# CoreBoard-001_2024-04-29.net
KiCad netlist of a schematic drawn in EasyEDA Pro
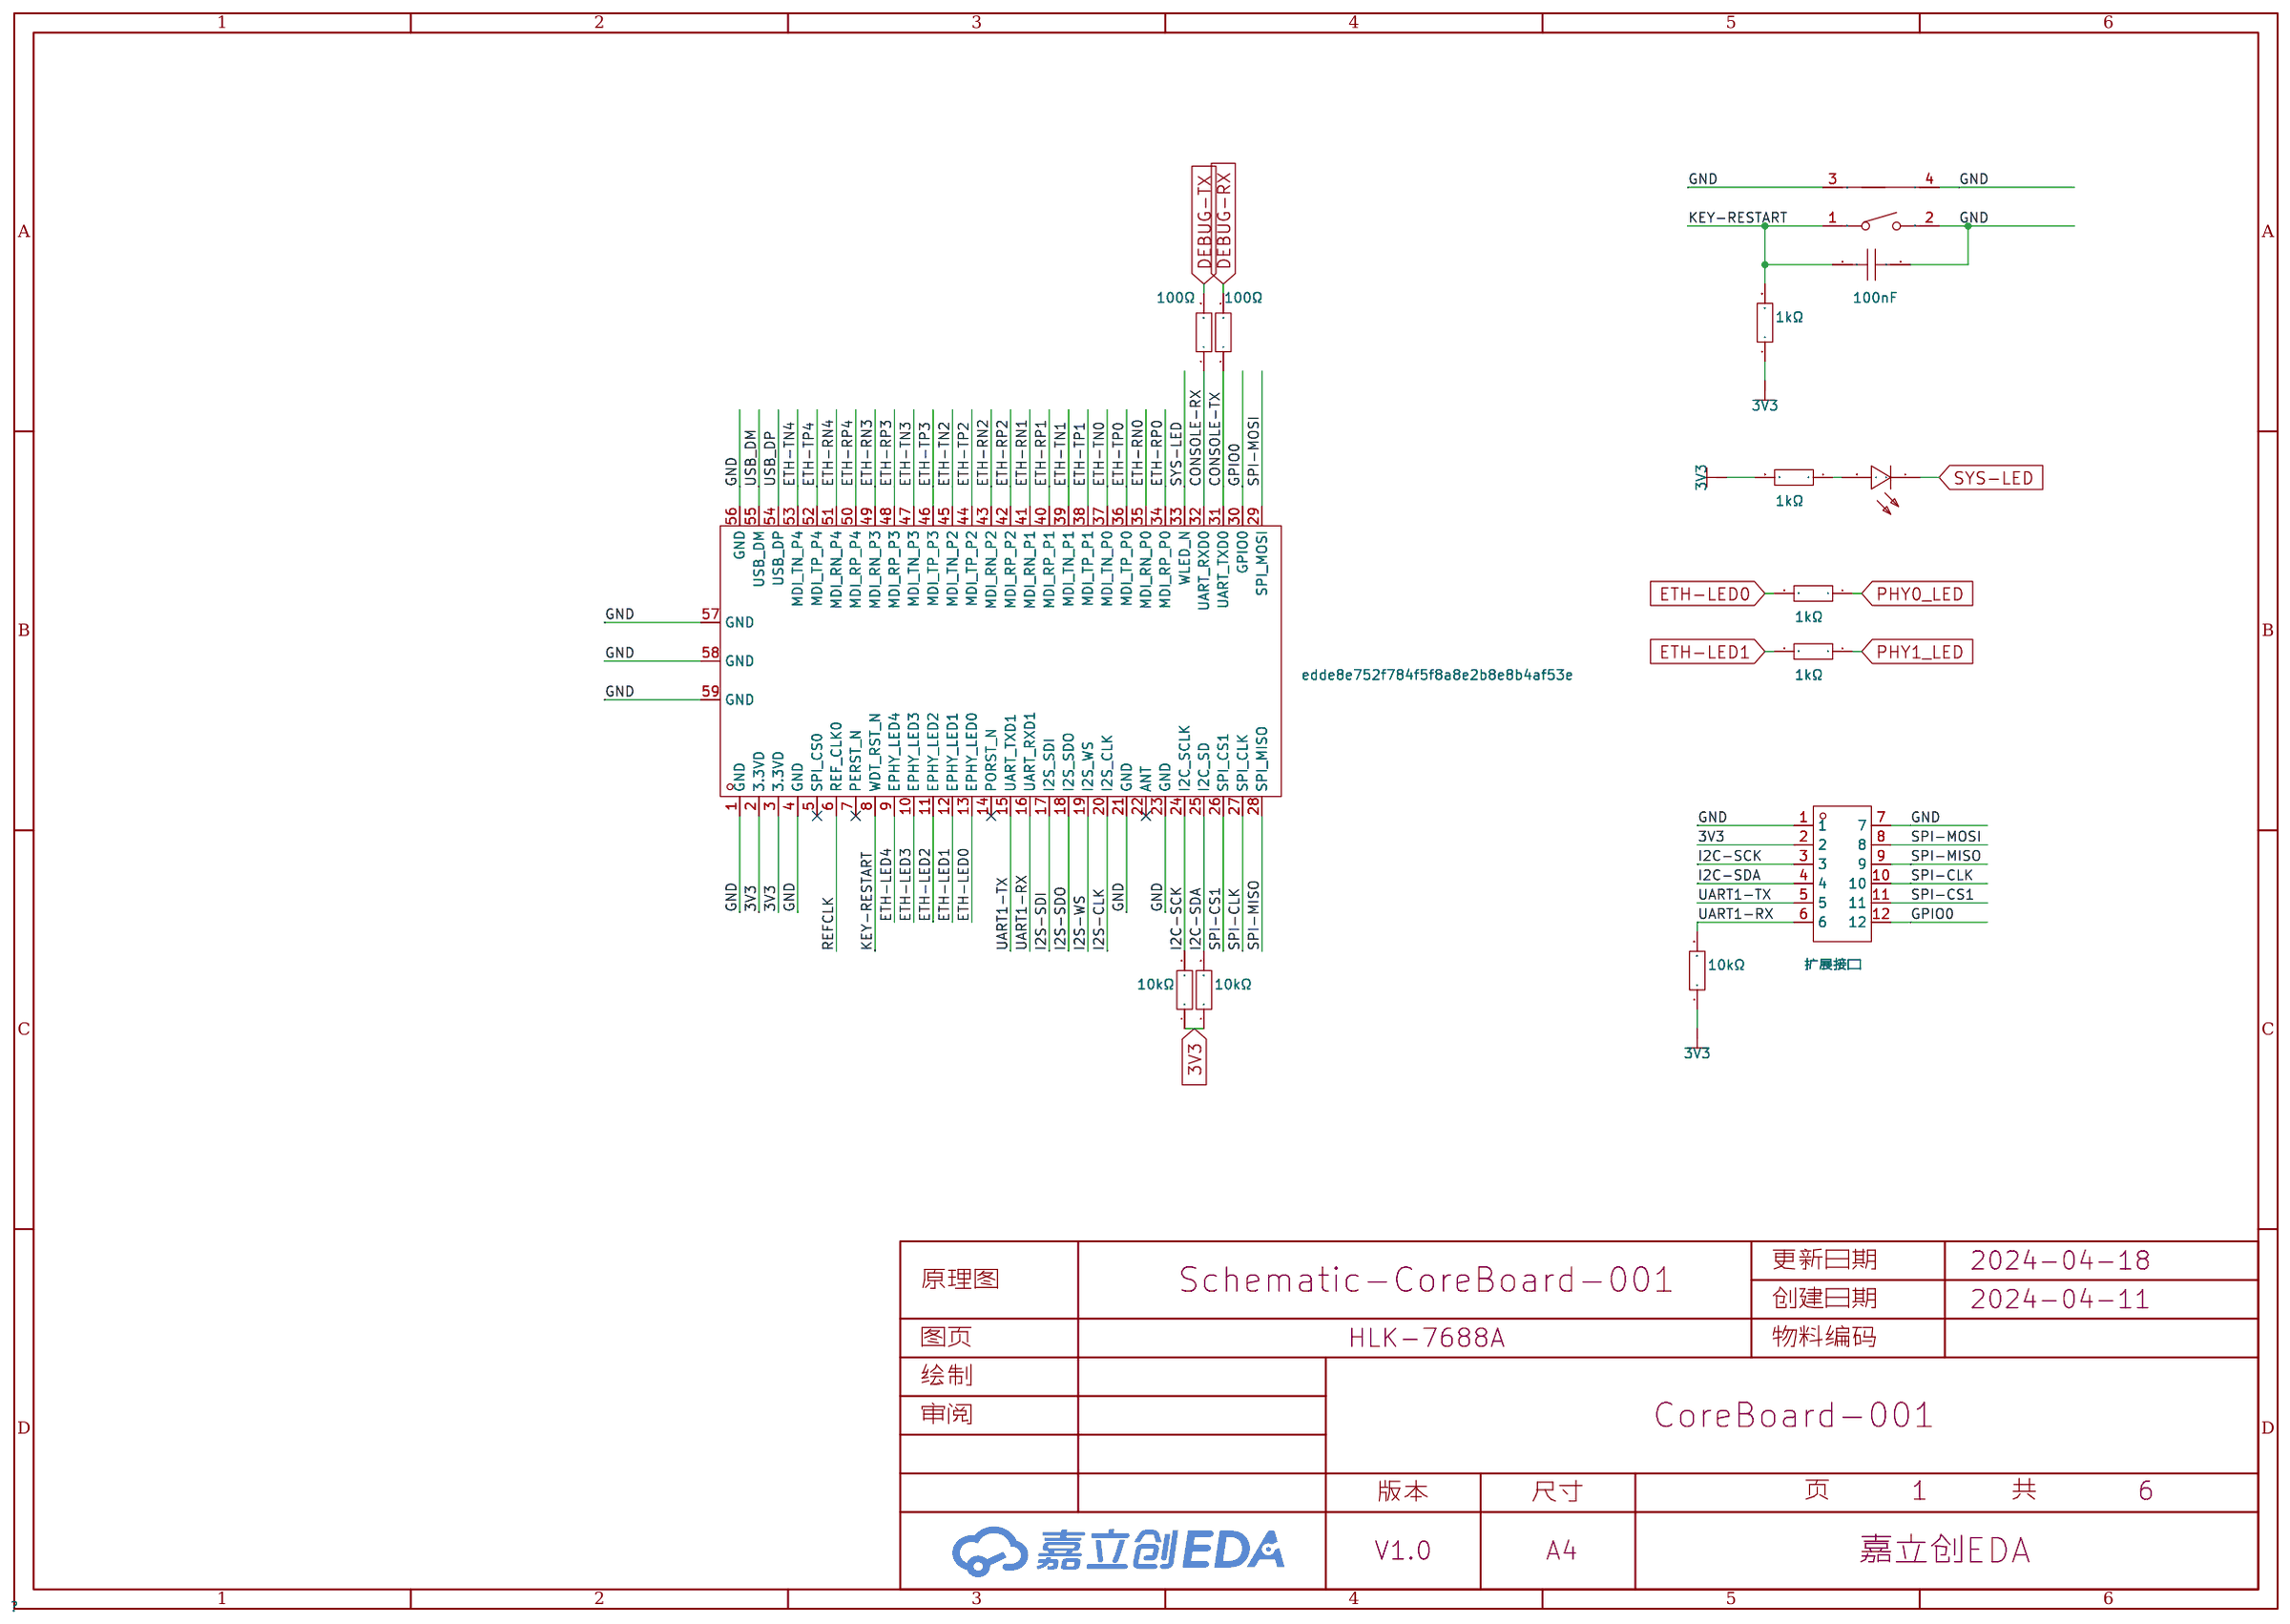
[diagram p0: HLK-7688A]
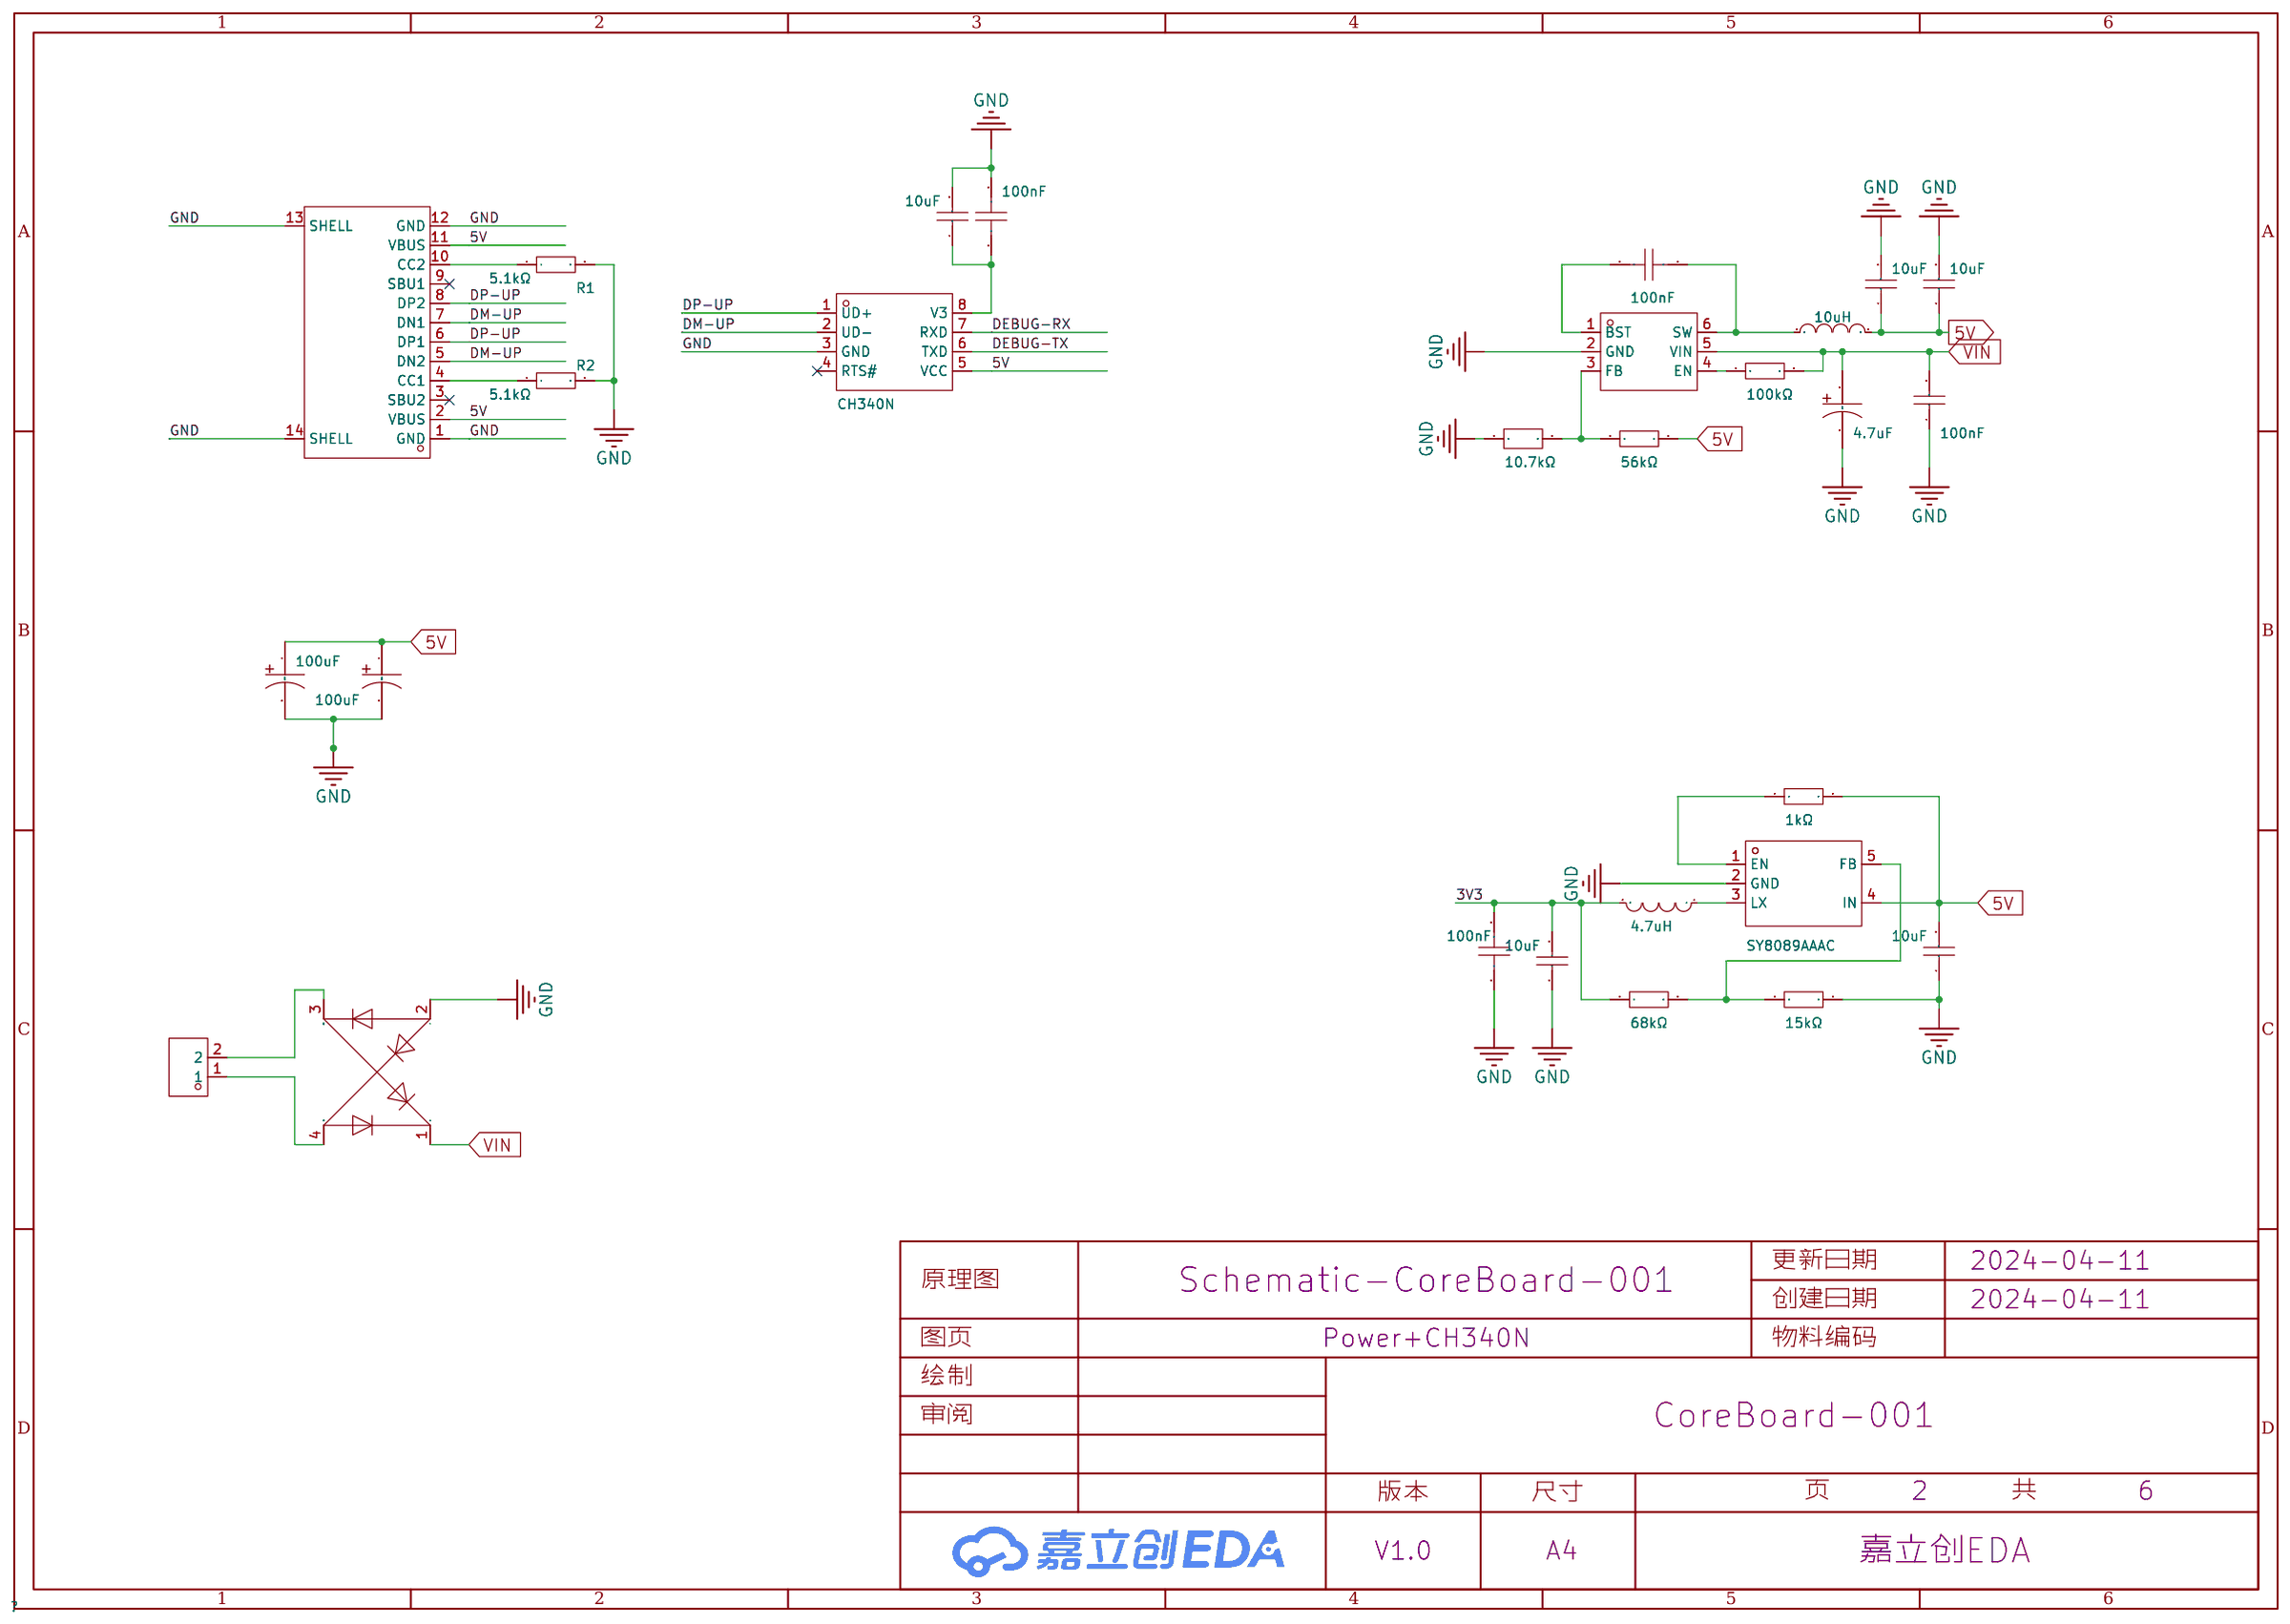
[diagram p1: Power+CH340N]
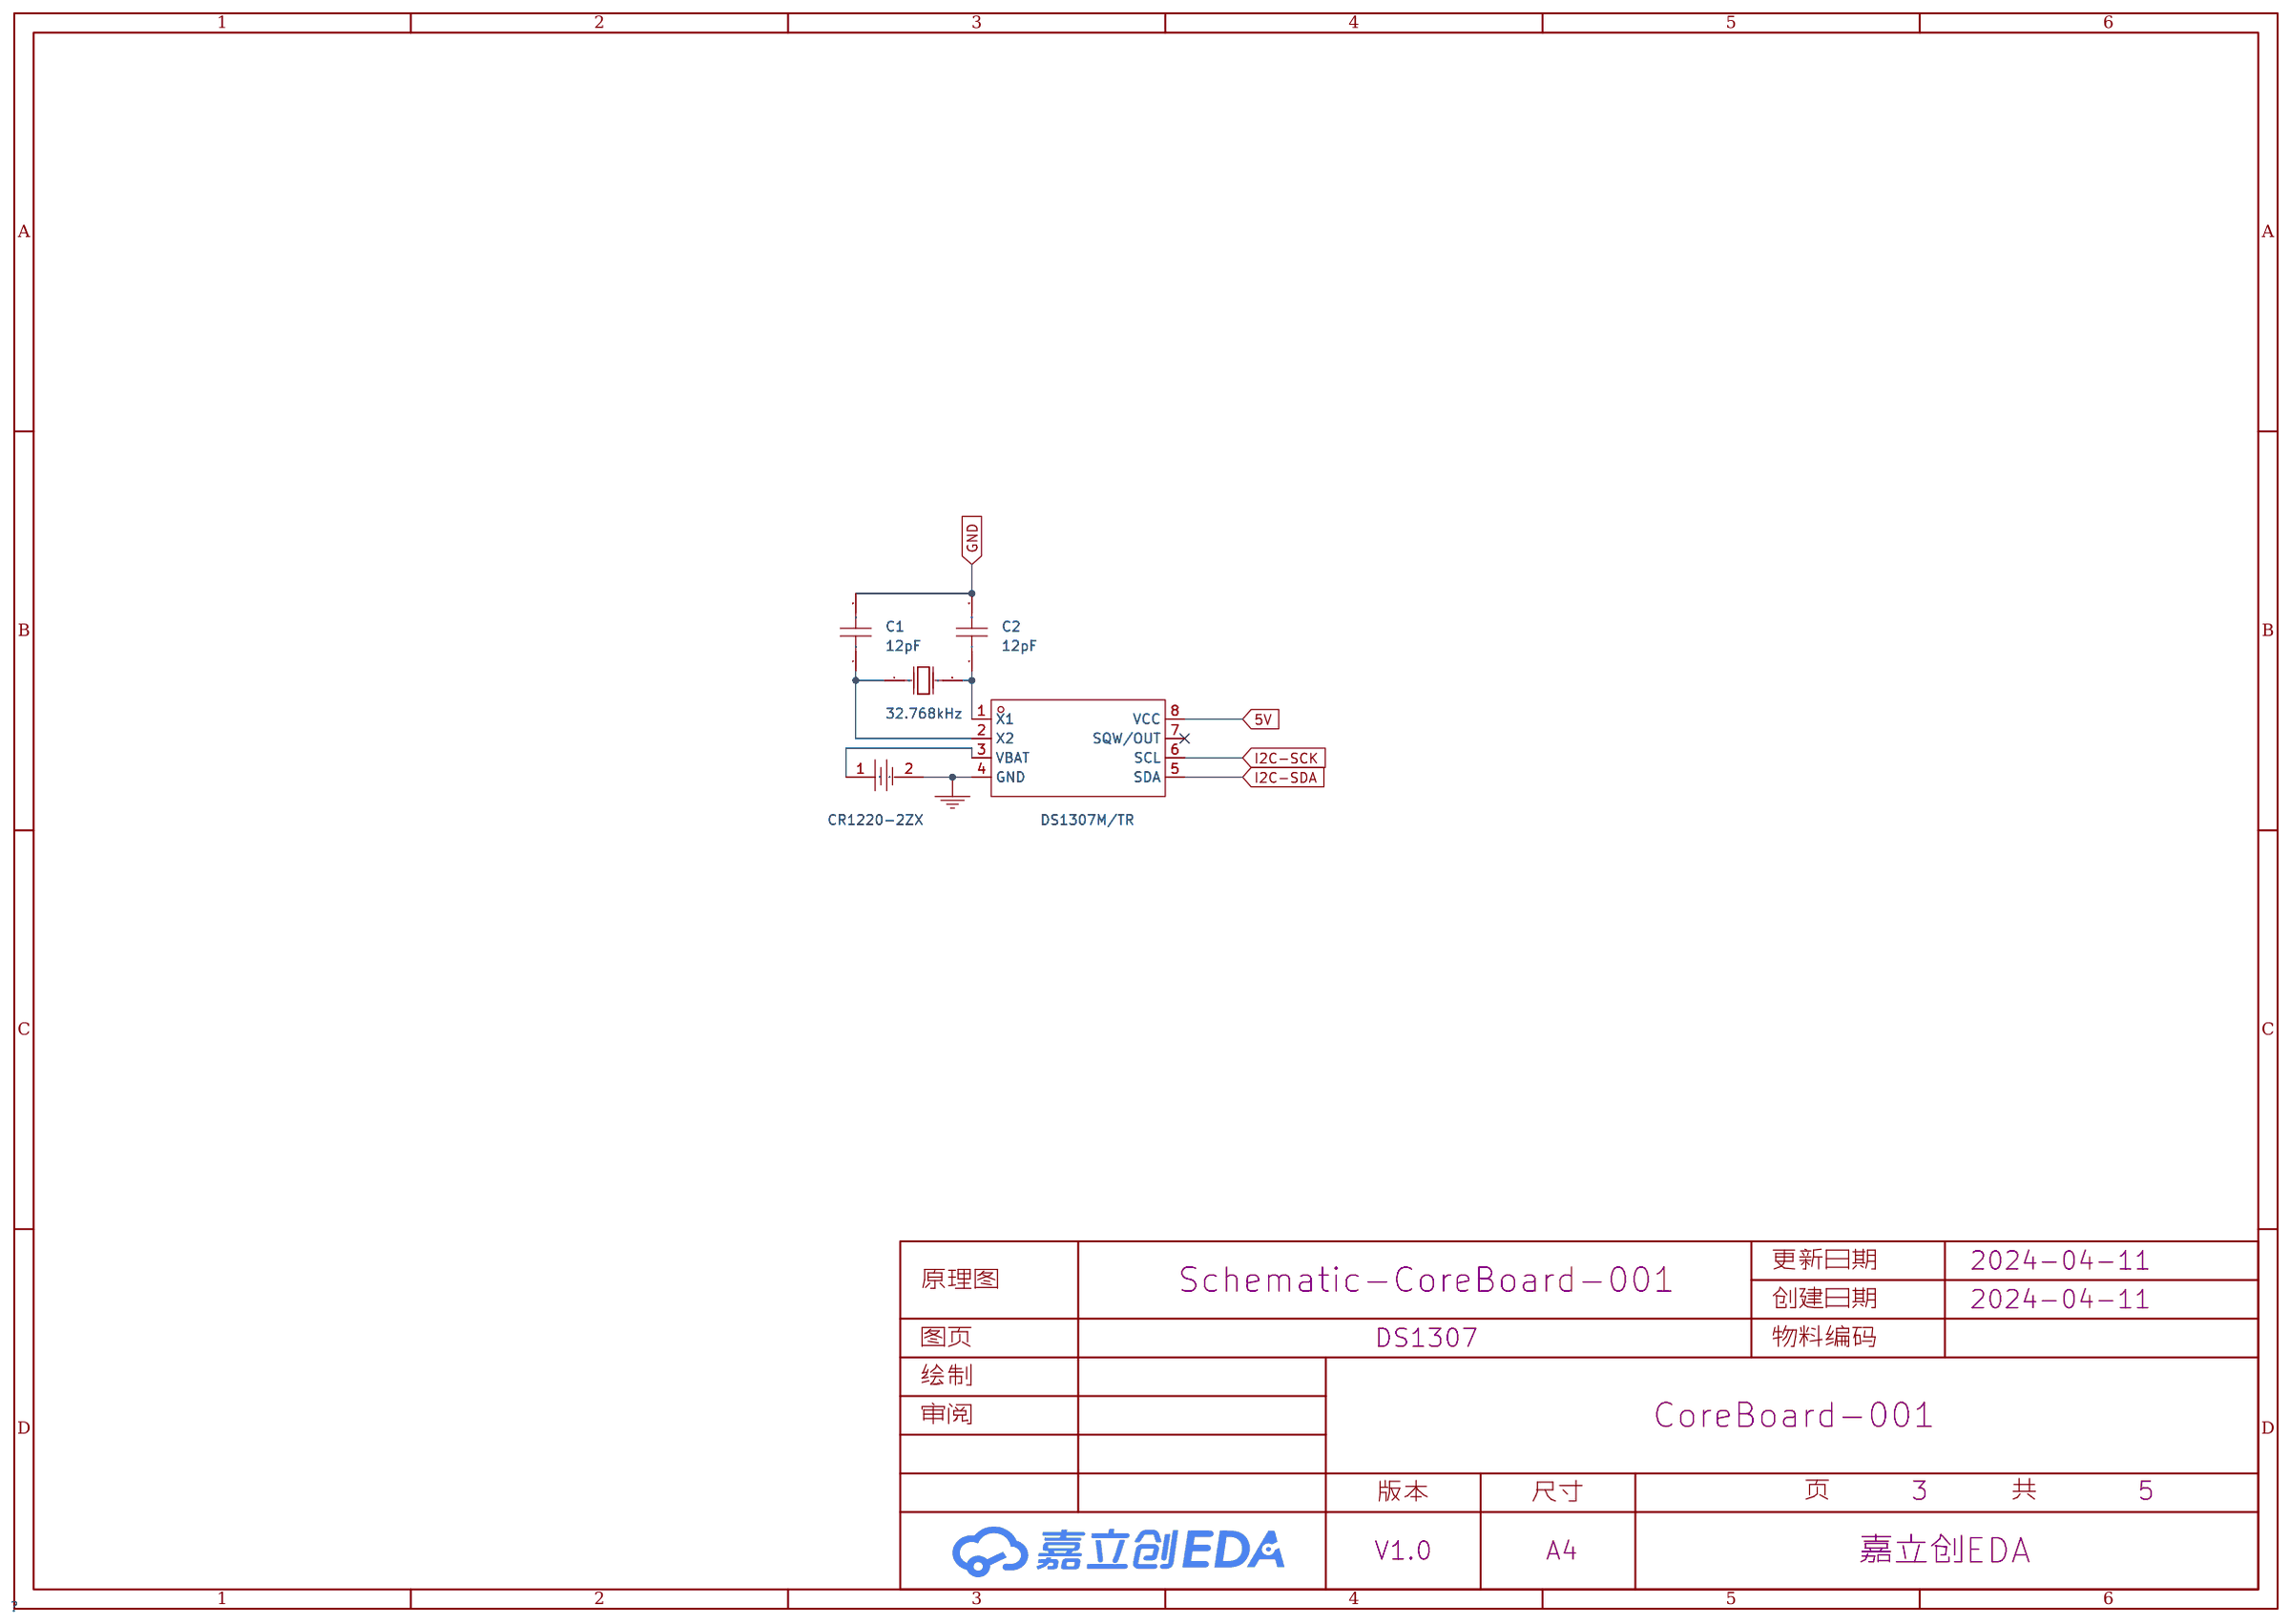
[diagram p2: DS1307]
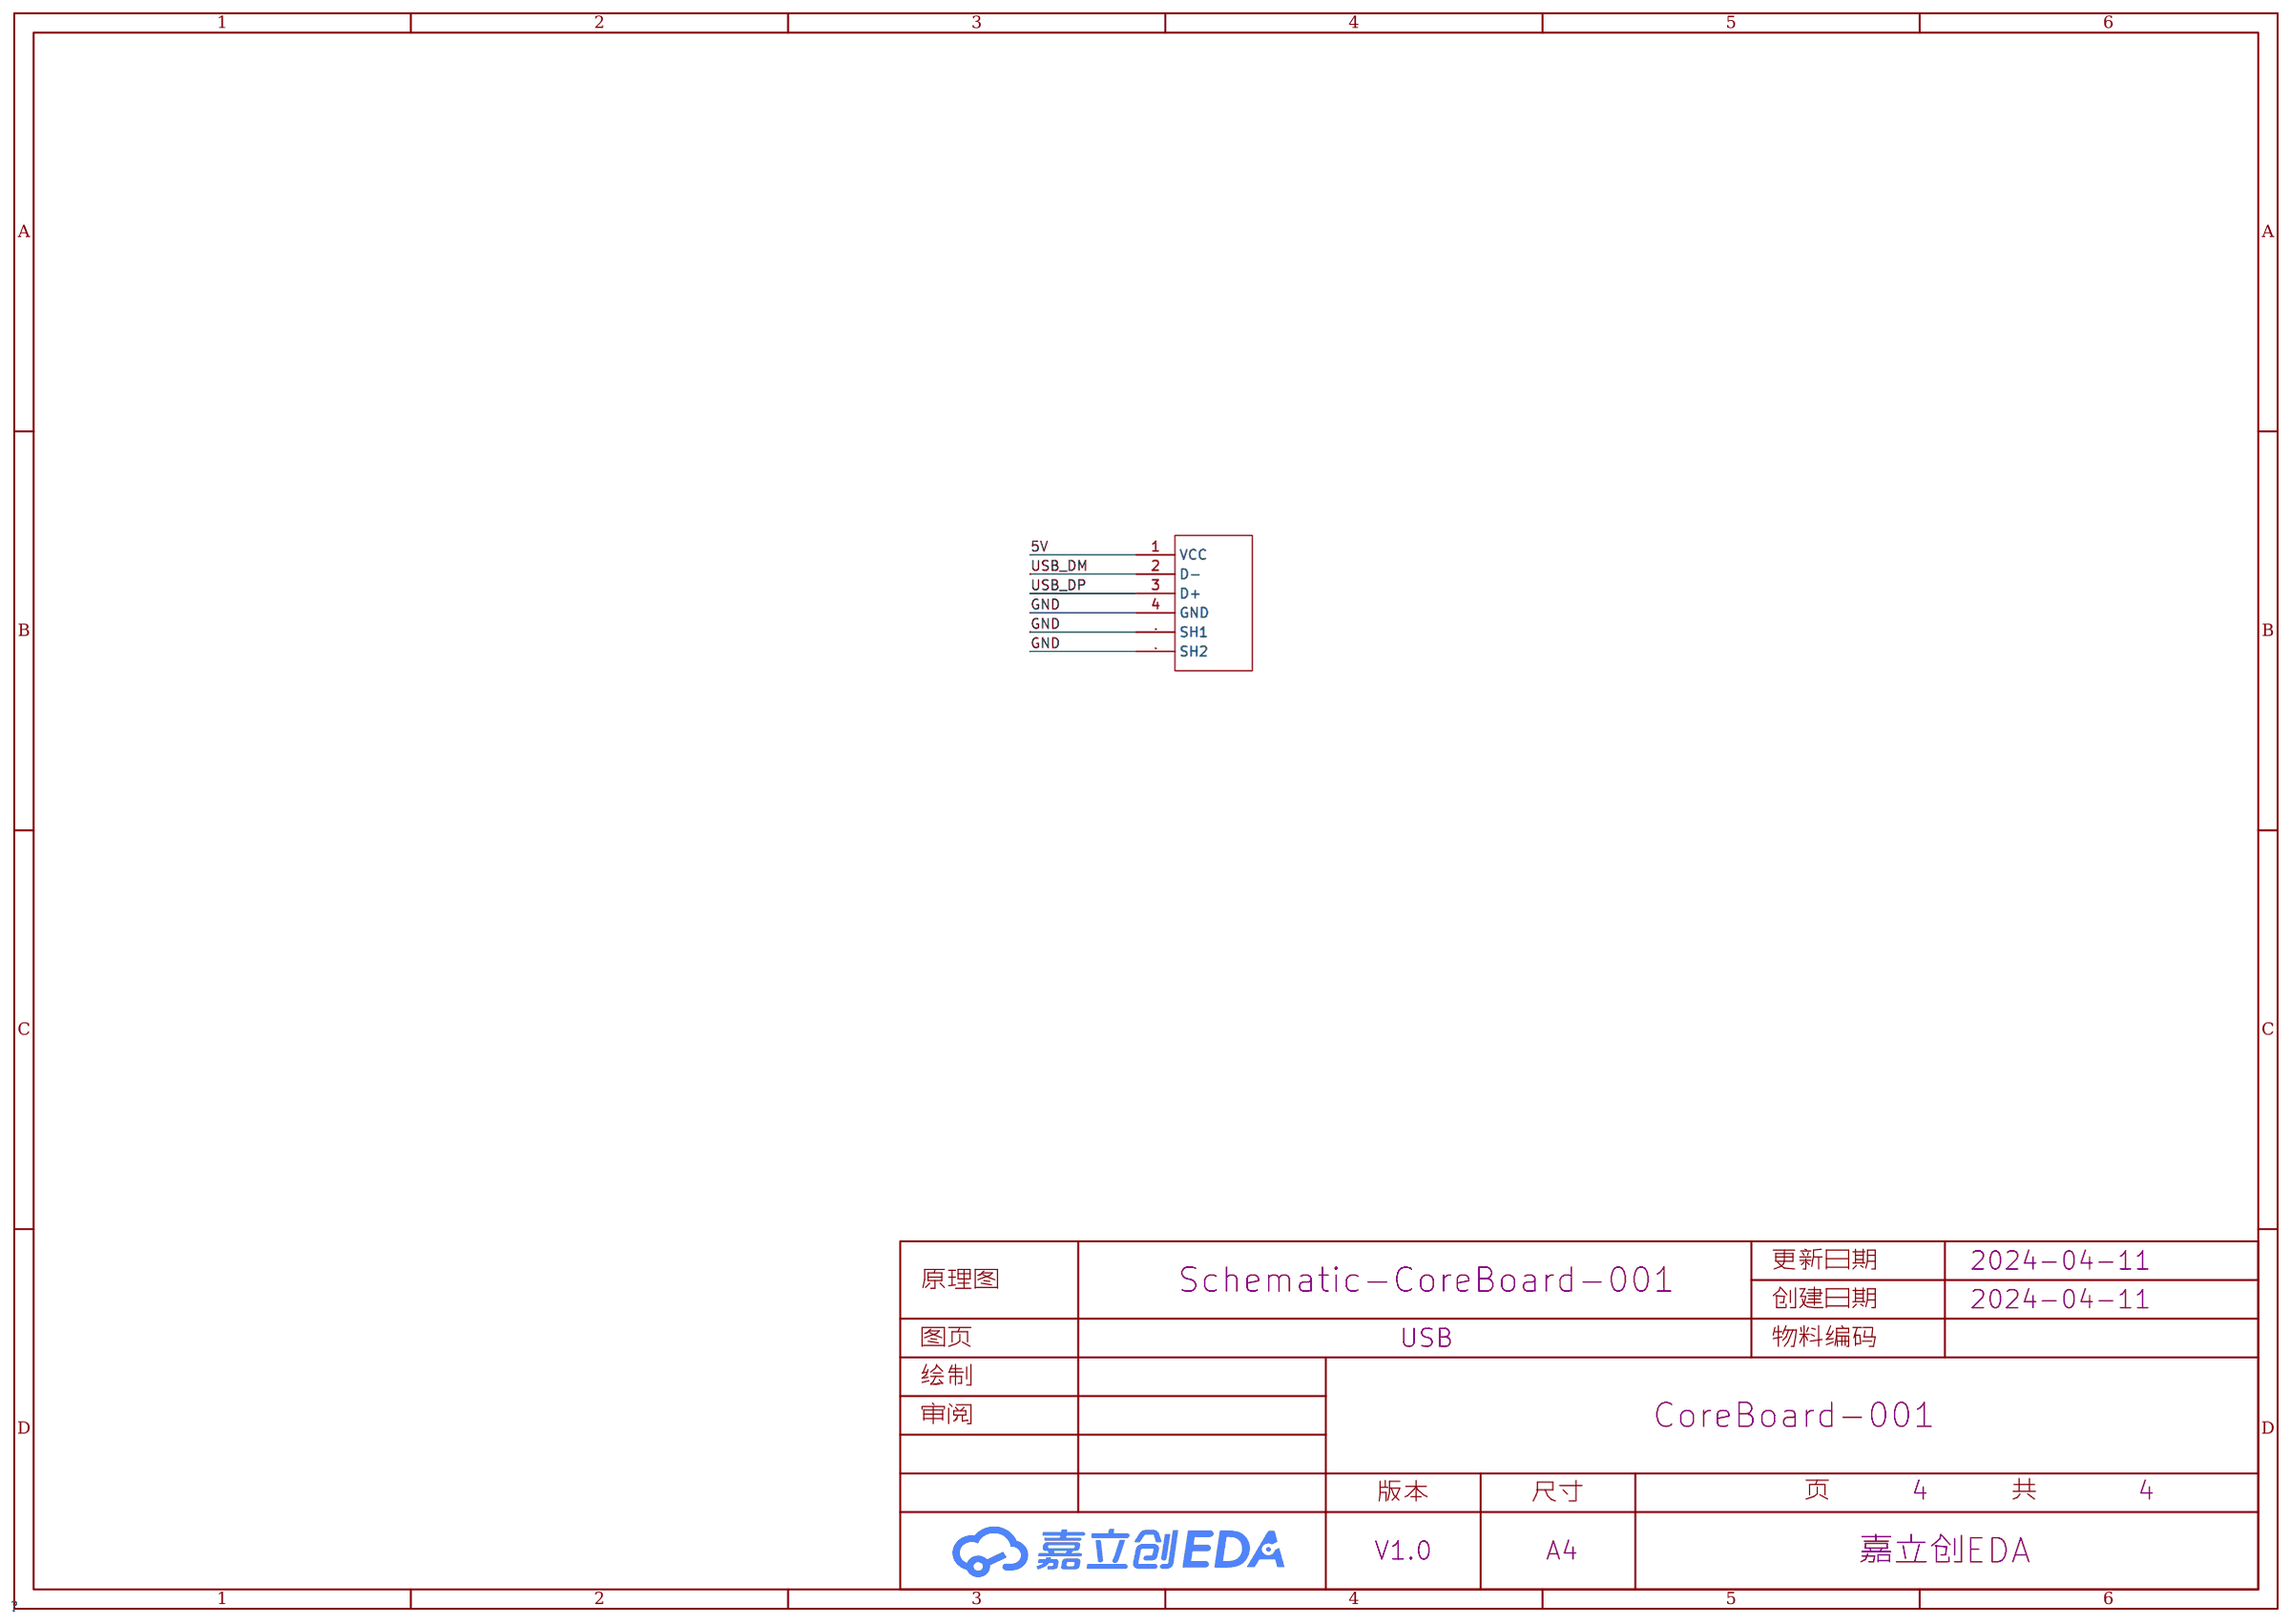
[diagram p3: USB]
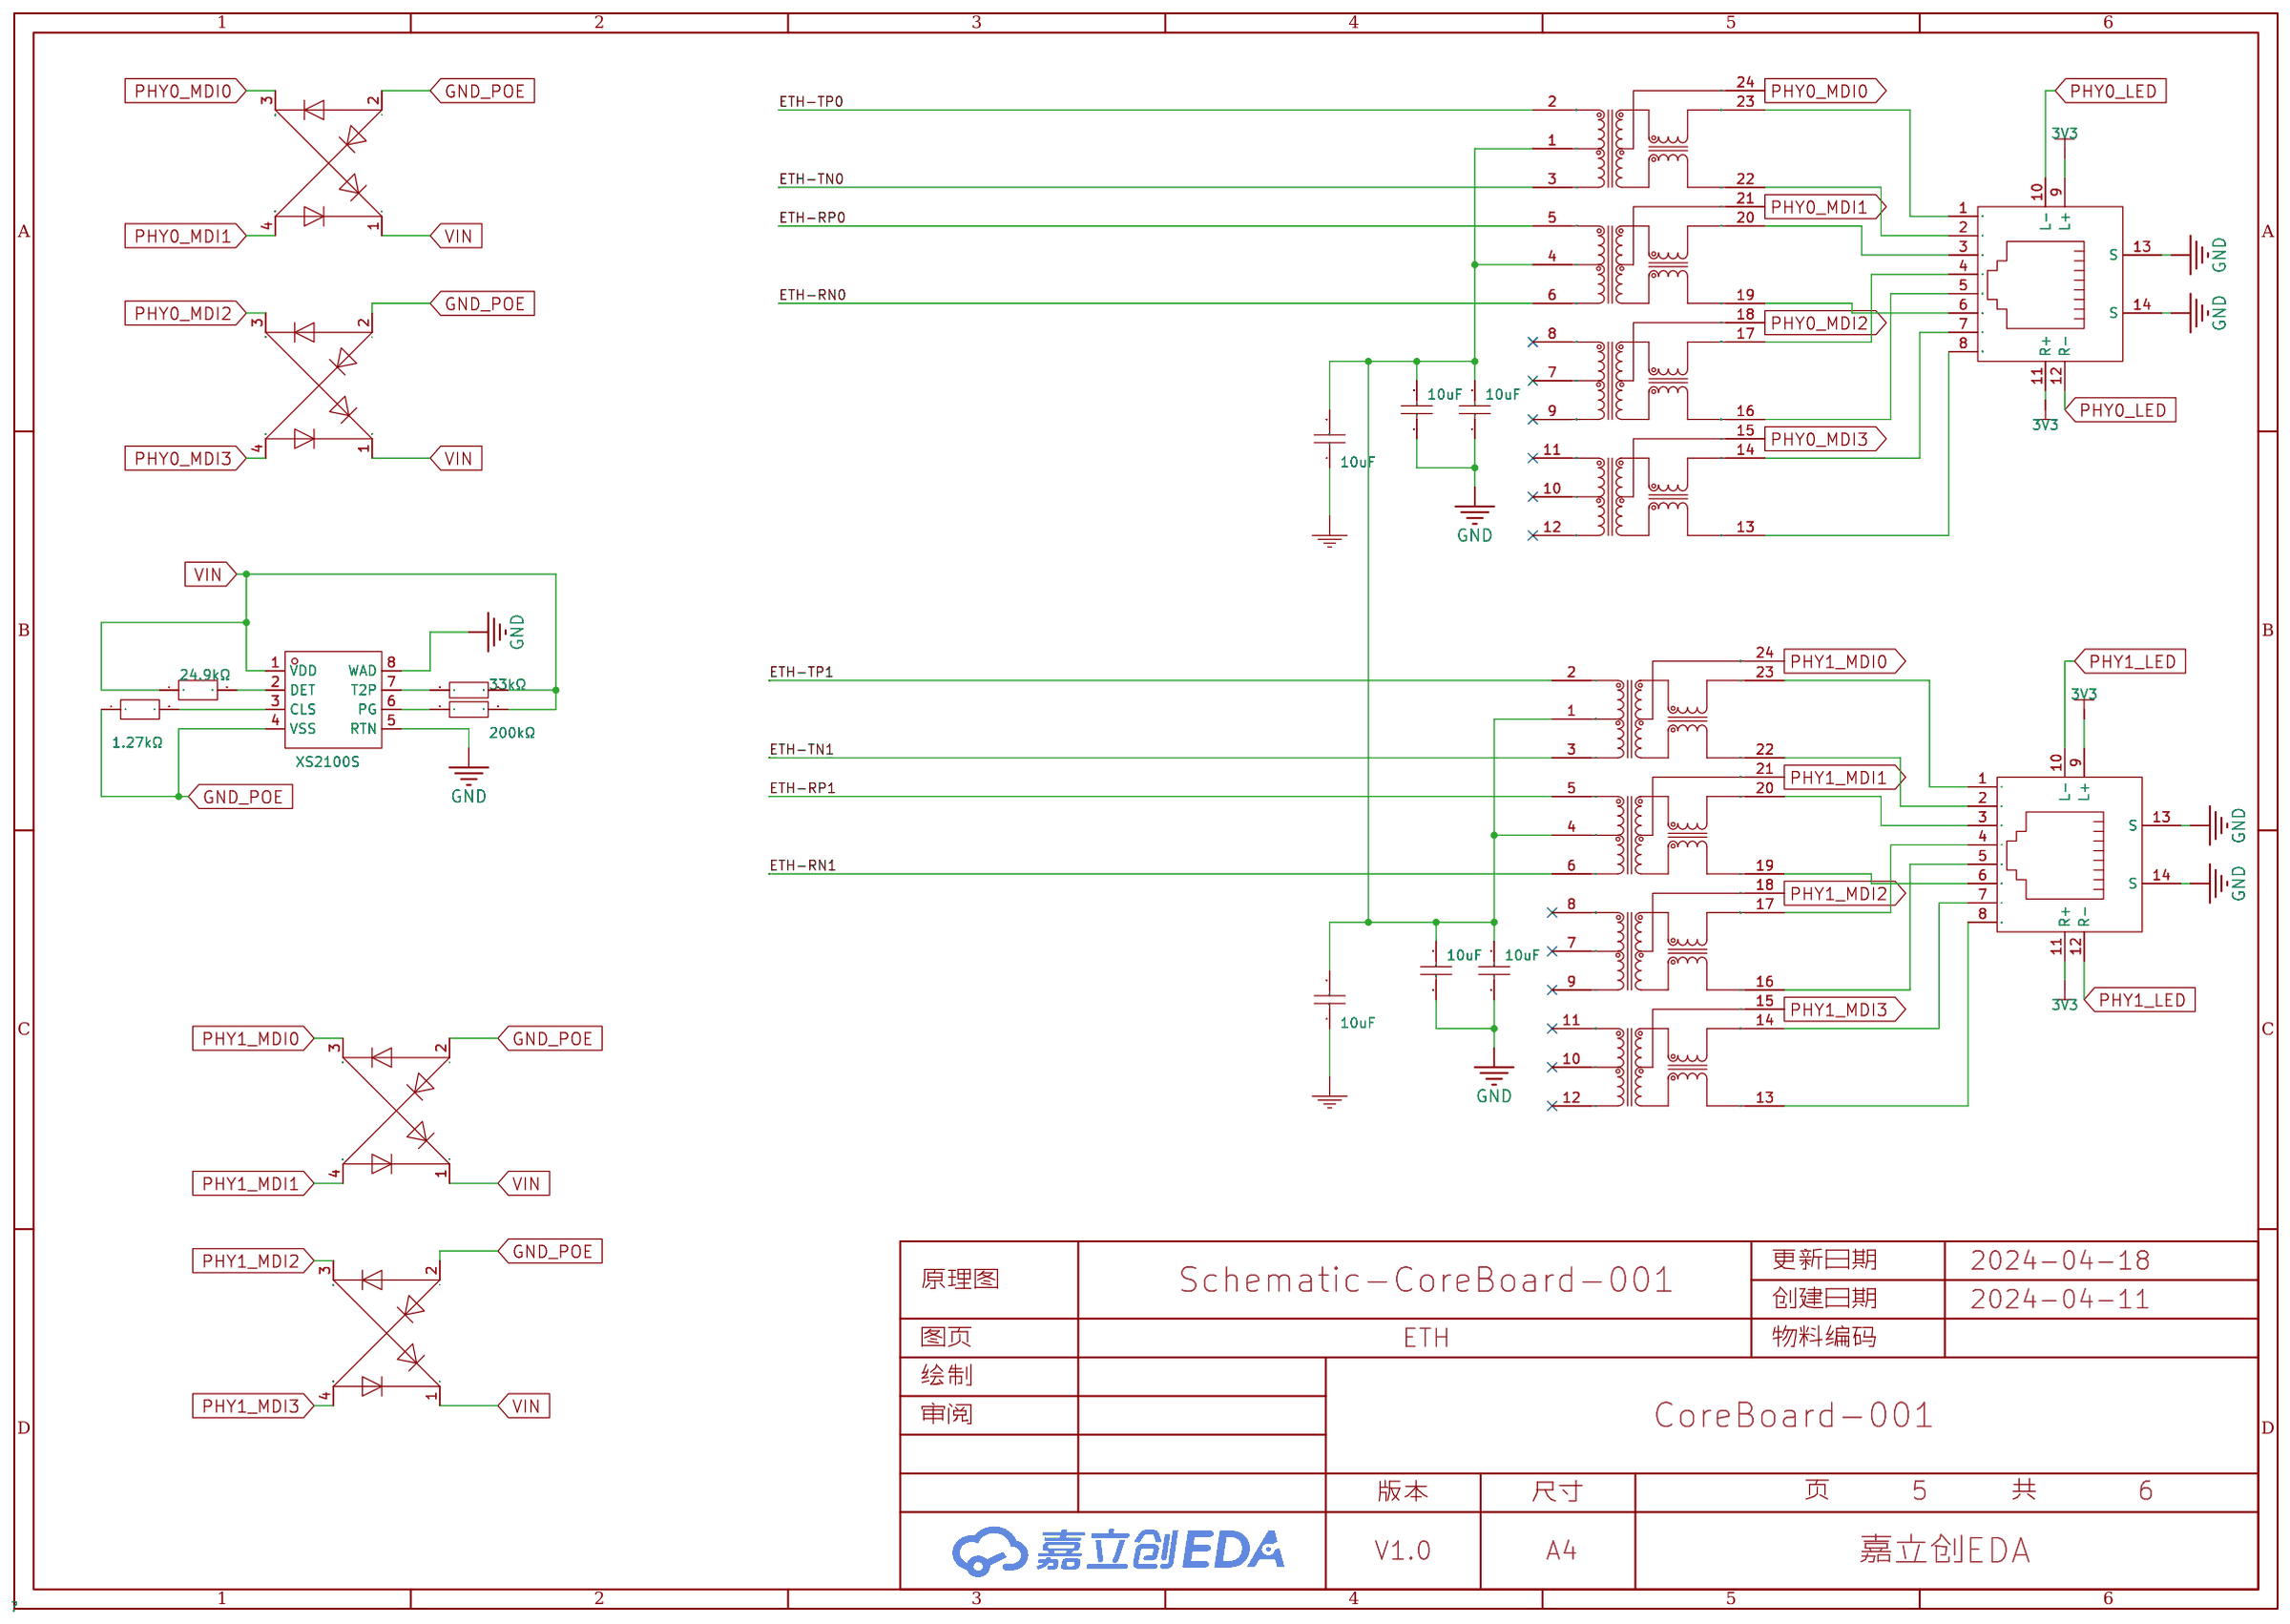
[diagram p4: ETH]
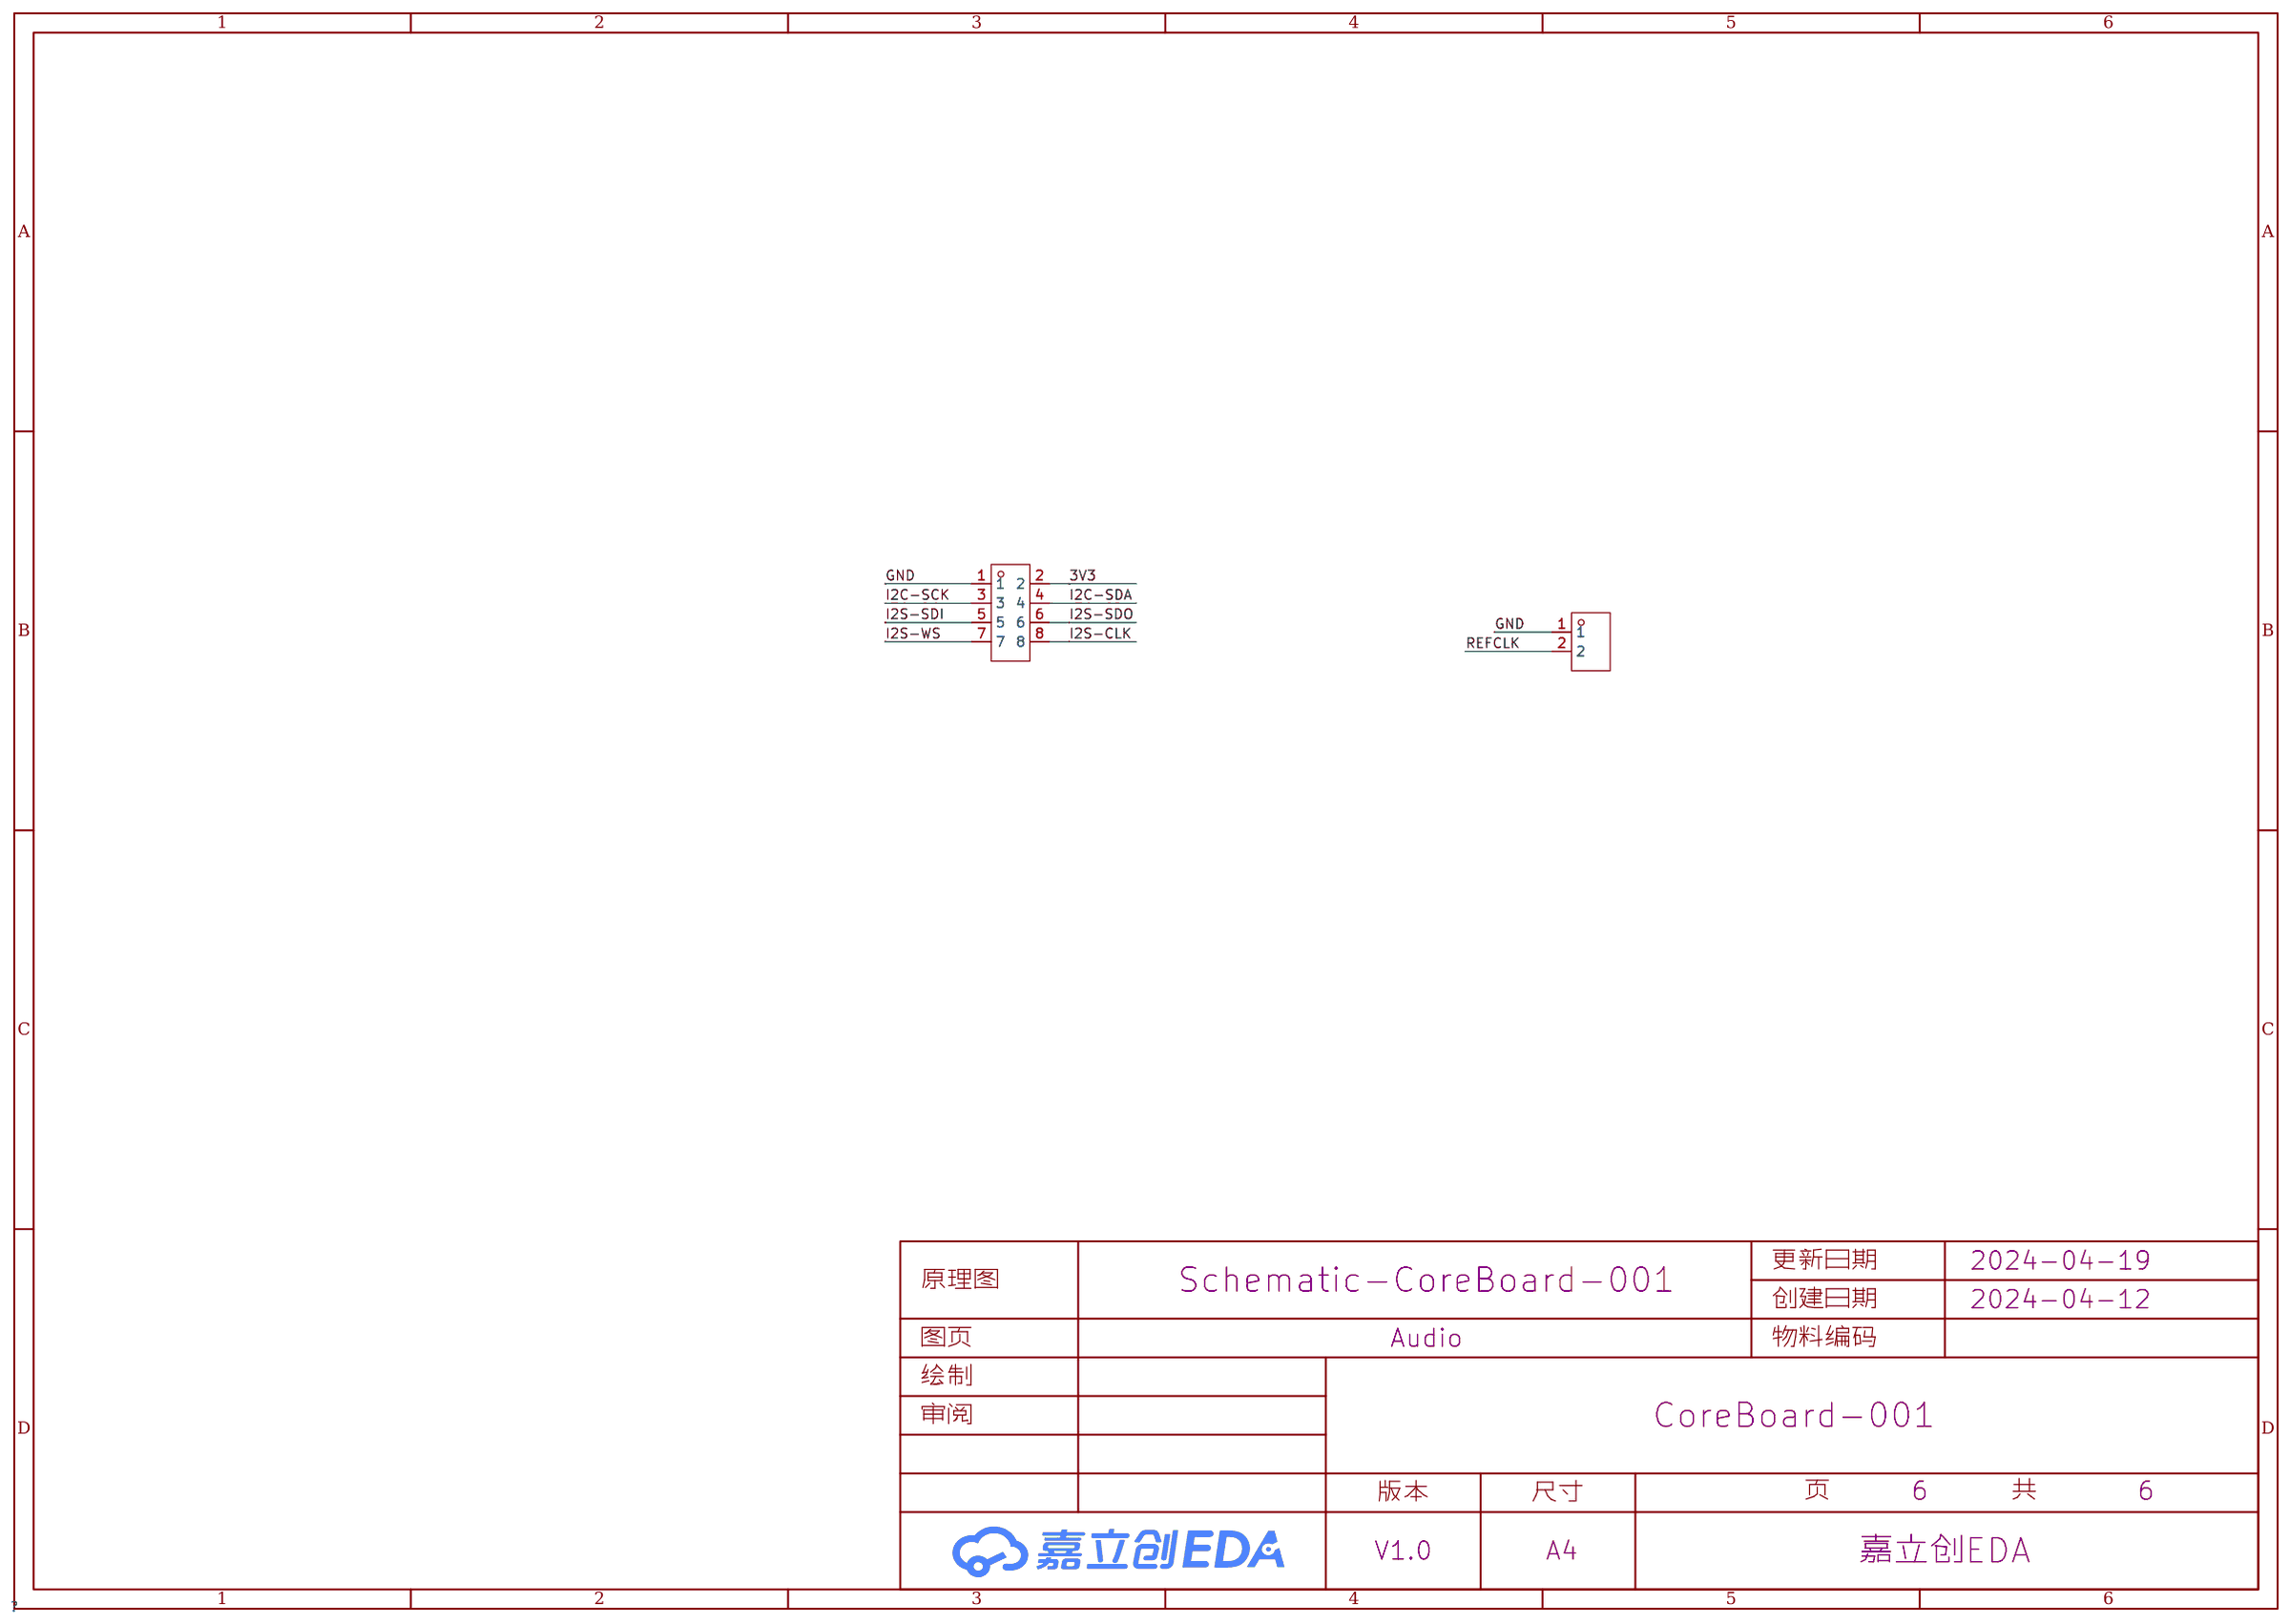
[diagram p5: Audio]

(export (version "E")
  (design (tool "Eeschema 10.0.6"))
  (components
    (comp (ref "C26")
      (value "100nF")
      (footprint "easyedapro:C0402")
      (description "容值:100nF;精度:±10%;额定电压:16V;材质(温度系数):X7R;")
      (fields
        (field (name "Manufacturer Part") "CC0402KRX7R7BB104")
        (field (name "Manufacturer") "YAGEO(国巨)")
      )
      (libsource (lib "easyedapro") (part "CC0402KRX7R7BB104"))
    )
    (comp (ref "CN2")
      (value "扩展接口")
      (footprint "easyedapro:CONN-TH_12P-P2.00_HCTL_HC-PHD")
      (fields (field (name "Manufacturer Part") "HC-PHD-2*6A") (field (name "Manufacturer") "HCTL(华灿天禄)"))
      (libsource (lib "easyedapro") (part "HC-PHD-2*6A"))
    )
    (comp (ref "LED1")
      (value "NCD0603R1")
      (footprint "easyedapro:LED0603-RD_RED")
      (fields (field (name "Manufacturer") "国星光电"))
      (libsource (lib "easyedapro") (part "FC-DA1608HRK-620D"))
    )
    (comp (ref "R3")
      (value "100Ω")
      (footprint "easyedapro:R0402")
      (description "电阻类型:厚膜电阻;阻值:100Ω;精度:±1%;功率:62.5mW;最大工作电压:50V;温度系数:±200ppm/°C;")
      (fields
        (field (name "Manufacturer Part") "0402WGF1000TCE")
        (field (name "Manufacturer") "UNI-ROYAL(厚声)")
      )
      (libsource (lib "easyedapro") (part "0402WGF1000TCE"))
    )
    (comp (ref "R4")
      (value "100Ω")
      (footprint "easyedapro:R0402")
      (description "电阻类型:厚膜电阻;阻值:100Ω;精度:±1%;功率:62.5mW;最大工作电压:50V;温度系数:±200ppm/°C;")
      (fields
        (field (name "Manufacturer Part") "0402WGF1000TCE")
        (field (name "Manufacturer") "UNI-ROYAL(厚声)")
      )
      (libsource (lib "easyedapro") (part "0402WGF1000TCE"))
    )
    (comp (ref "R5")
      (value "10kΩ")
      (footprint "easyedapro:R0402")
      (description "电阻类型:厚膜电阻;阻值:10kΩ;精度:±1%;功率:62.5mW;最大工作电压:50V;温度系数:±100ppm/°C;")
      (fields (field (name "Manufacturer Part") "RC0402FR-0710KL") (field (name "Manufacturer") "YAGEO(国巨)"))
      (libsource (lib "easyedapro") (part "RC0402FR-0710KL"))
    )
    (comp (ref "R6")
      (value "10kΩ")
      (footprint "easyedapro:R0402")
      (description "电阻类型:厚膜电阻;阻值:10kΩ;精度:±1%;功率:62.5mW;最大工作电压:50V;温度系数:±100ppm/°C;")
      (fields (field (name "Manufacturer Part") "RC0402FR-0710KL") (field (name "Manufacturer") "YAGEO(国巨)"))
      (libsource (lib "easyedapro") (part "RC0402FR-0710KL"))
    )
    (comp (ref "R14")
      (value "1kΩ")
      (footprint "easyedapro:R0402")
      (description "阻值:1kΩ;精度:±1%;功率:62.5mW;温度系数:±100ppm/°C;电阻类型:厚膜电阻;")
      (fields
        (field (name "Manufacturer Part") "0402WGF1001TCE")
        (field (name "Manufacturer") "UNI-ROYAL(厚声)")
      )
      (libsource (lib "easyedapro") (part "0402WGF1001TCE"))
    )
    (comp (ref "R15")
      (value "1kΩ")
      (footprint "easyedapro:R0402")
      (description "阻值:1kΩ;精度:±1%;功率:62.5mW;温度系数:±100ppm/°C;电阻类型:厚膜电阻;")
      (fields
        (field (name "Manufacturer Part") "0402WGF1001TCE")
        (field (name "Manufacturer") "UNI-ROYAL(厚声)")
      )
      (libsource (lib "easyedapro") (part "0402WGF1001TCE"))
    )
    (comp (ref "R21")
      (value "1kΩ")
      (footprint "easyedapro:R0402")
      (description "阻值:1kΩ;精度:±1%;功率:62.5mW;温度系数:±100ppm/°C;电阻类型:厚膜电阻;")
      (fields
        (field (name "Manufacturer Part") "0402WGF1001TCE")
        (field (name "Manufacturer") "UNI-ROYAL(厚声)")
      )
      (libsource (lib "easyedapro") (part "0402WGF1001TCE"))
    )
    (comp (ref "R22")
      (value "1kΩ")
      (footprint "easyedapro:R0402")
      (description "阻值:1kΩ;精度:±1%;功率:62.5mW;温度系数:±100ppm/°C;电阻类型:厚膜电阻;")
      (fields
        (field (name "Manufacturer Part") "0402WGF1001TCE")
        (field (name "Manufacturer") "UNI-ROYAL(厚声)")
      )
      (libsource (lib "easyedapro") (part "0402WGF1001TCE"))
    )
    (comp (ref "R23")
      (value "10kΩ")
      (footprint "easyedapro:R0402")
      (description "电阻类型:厚膜电阻;阻值:10kΩ;精度:±1%;功率:62.5mW;最大工作电压:50V;温度系数:±100ppm/°C;")
      (fields (field (name "Manufacturer Part") "RC0402FR-0710KL") (field (name "Manufacturer") "YAGEO(国巨)"))
      (libsource (lib "easyedapro") (part "RC0402FR-0710KL"))
    )
    (comp (ref "SW1")
      (value "TS665ZJ")
      (footprint "easyedapro:SW-TH_TS665ZJ")
      (fields (field (name "Manufacturer") "SHOU HAN(首韩)"))
      (libsource (lib "easyedapro") (part "TS665ZJ"))
    )
    (comp (ref "U1")
      (value "2.412GHz；2.483GHz")
      (footprint "easyedapro:WIRELM-SMD_HLK-7688A")
      (description "核心处理器:MT7688AN芯片;频率:2.412GHz；2.483GHz;天线形式:-;发射功率:14dBm~22dBm;接收灵敏度:-;")
      (fields (field (name "Manufacturer Part") "HLK-7688A") (field (name "Manufacturer") "HI-LINK(海凌科)"))
      (libsource (lib "easyedapro") (part "HLK-7688A"))
    )
    (comp (ref "C15")
      (value "10uF")
      (footprint "easyedapro:C0402")
      (description "容值:10uF;精度:±20%;额定电压:6.3V;材质(温度系数):X5R;")
      (fields
        (field (name "Manufacturer Part") "CL05A106MQ5NUNC")
        (field (name "Manufacturer") "SAMSUNG(三星)")
      )
      (libsource (lib "easyedapro") (part "CL05A106MQ5NUNC"))
    )
    (comp (ref "C16")
      (value "10uF")
      (footprint "easyedapro:C0402")
      (description "容值:10uF;精度:±20%;额定电压:6.3V;材质(温度系数):X5R;")
      (fields
        (field (name "Manufacturer Part") "CL05A106MQ5NUNC")
        (field (name "Manufacturer") "SAMSUNG(三星)")
      )
      (libsource (lib "easyedapro") (part "CL05A106MQ5NUNC"))
    )
    (comp (ref "C17")
      (value "100nF")
      (footprint "easyedapro:C0402")
      (description "容值:100nF;精度:±10%;额定电压:16V;材质(温度系数):X7R;")
      (fields
        (field (name "Manufacturer Part") "CC0402KRX7R7BB104")
        (field (name "Manufacturer") "YAGEO(国巨)")
      )
      (libsource (lib "easyedapro") (part "CC0402KRX7R7BB104"))
    )
    (comp (ref "C18")
      (value "4.7uF")
      (footprint "easyedapro:CAP-SMD_BD4.0-L4.3-W4.3-FD-A")
      (description "容值:4.7uF;精度:±20%;额定电压:50V;纹波电流:14mA@120Hz;等效串联电阻:-;")
      (fields (field (name "Manufacturer Part") "VT1H4R7M0405") (field (name "Manufacturer") "ROQANG(容强)"))
      (libsource (lib "easyedapro") (part "VT1H4R7M0405"))
    )
    (comp (ref "C19")
      (value "100nF")
      (footprint "easyedapro:C0603")
      (description "容值:100nF;精度:±10%;额定电压:50V;材质(温度系数):X7R;")
      (fields (field (name "Manufacturer Part") "0603B104K500NT") (field (name "Manufacturer") "FH(风华)"))
      (libsource (lib "easyedapro") (part "0603B104K500NT"))
    )
    (comp (ref "C20")
      (value "10uF")
      (footprint "easyedapro:C0402")
      (description "容值:10uF;精度:±20%;额定电压:6.3V;材质(温度系数):X5R;")
      (fields
        (field (name "Manufacturer Part") "CL05A106MQ5NUNC")
        (field (name "Manufacturer") "SAMSUNG(三星)")
      )
      (libsource (lib "easyedapro") (part "CL05A106MQ5NUNC"))
    )
    (comp (ref "C21")
      (value "10uF")
      (footprint "easyedapro:C0402")
      (description "容值:10uF;精度:±20%;额定电压:6.3V;材质(温度系数):X5R;")
      (fields
        (field (name "Manufacturer Part") "CL05A106MQ5NUNC")
        (field (name "Manufacturer") "SAMSUNG(三星)")
      )
      (libsource (lib "easyedapro") (part "CL05A106MQ5NUNC"))
    )
    (comp (ref "C22")
      (value "100uF")
      (footprint "easyedapro:CAP-SMD_BD6.3-L6.6-W6.6-FD")
      (description "容值:100uF;精度:±20%;额定电压:16V;纹波电流:-;等效串联电阻:-;")
      (fields (field (name "Manufacturer Part") "VEZ101M1CTR-0605") (field (name "Manufacturer") "lelon(立隆)"))
      (libsource (lib "easyedapro") (part "VEZ101M1C0605-TRO"))
    )
    (comp (ref "C23")
      (value "100uF")
      (footprint "easyedapro:CAP-SMD_BD6.3-L6.6-W6.6-FD")
      (description "容值:100uF;精度:±20%;额定电压:16V;纹波电流:-;等效串联电阻:-;")
      (fields (field (name "Manufacturer Part") "VEZ101M1CTR-0605") (field (name "Manufacturer") "lelon(立隆)"))
      (libsource (lib "easyedapro") (part "VEZ101M1C0605-TRO"))
    )
    (comp (ref "C24")
      (value "100nF")
      (footprint "easyedapro:C0402")
      (description "容值:100nF;精度:±10%;额定电压:16V;材质(温度系数):X7R;")
      (fields
        (field (name "Manufacturer Part") "CC0402KRX7R7BB104")
        (field (name "Manufacturer") "YAGEO(国巨)")
      )
      (libsource (lib "easyedapro") (part "CC0402KRX7R7BB104"))
    )
    (comp (ref "C25")
      (value "10uF")
      (footprint "easyedapro:C0402")
      (description "容值:10uF;精度:±20%;额定电压:6.3V;材质(温度系数):X5R;")
      (fields
        (field (name "Manufacturer Part") "CL05A106MQ5NUNC")
        (field (name "Manufacturer") "SAMSUNG(三星)")
      )
      (libsource (lib "easyedapro") (part "CL05A106MQ5NUNC"))
    )
    (comp (ref "C27")
      (value "100nF")
      (footprint "easyedapro:C0402")
      (description "容值:100nF;精度:±10%;额定电压:16V;材质(温度系数):X7R;")
      (fields
        (field (name "Manufacturer Part") "CC0402KRX7R7BB104")
        (field (name "Manufacturer") "YAGEO(国巨)")
      )
      (libsource (lib "easyedapro") (part "CC0402KRX7R7BB104"))
    )
    (comp (ref "CN1")
      (value "DB2ERC-3.81-2P-GN")
      (footprint "easyedapro:CONN-TH_2P-P3.81_DB2ERC-3.81-2P")
      (fields (field (name "Manufacturer") "DORABO(地博电气)"))
      (libsource (lib "easyedapro") (part "DB2ERC-3.81-2P"))
    )
    (comp (ref "D1")
      (value "MB10S")
      (footprint "easyedapro:MBS_L4.7-W3.8-P2.40-LS7.0-TL")
      (description "正向压降(Vf):1.1V@400mA;直流反向耐压(Vr):1kV;平均整流电流(Io):1A;正向浪涌电流(Ifsm):35A;")
      (fields (field (name "Manufacturer") "MDD"))
      (libsource (lib "easyedapro") (part "MB10S_C2488"))
    )
    (comp (ref "L1")
      (value "4.7uH")
      (footprint "easyedapro:IND-SMD_L4.0-W4.0")
      (description "直流电阻(DCR):78mΩ;精度:±20%;电感值:4.7uH;额定电流:2A;")
      (fields (field (name "Manufacturer Part") "SWPA4030S4R7MT") (field (name "Manufacturer") "Sunlord(顺络)"))
      (libsource (lib "easyedapro") (part "SWPA4030S4R7MT"))
    )
    (comp (ref "L2")
      (value "10uH")
      (footprint "easyedapro:IND-SMD_L4.4-W4.2")
      (description "电感值:10uH;精度:±20%;额定电流:1.6A;类型:一体成型电感;饱和电流(Isat):2.2A;")
      (fields (field (name "Manufacturer Part") "FXL0420-100-M") (field (name "Manufacturer") "cjiang(长江微电)"))
      (libsource (lib "easyedapro") (part "FXL0420-100-M"))
    )
    (comp (ref "R1")
      (value "5.1kΩ")
      (footprint "easyedapro:R0402")
      (description "阻值:5.1kΩ;精度:±1%;功率:62.5mW;温度系数:±100ppm/°C;电阻类型:厚膜电阻;")
      (fields
        (field (name "Manufacturer Part") "0402WGF5101TCE")
        (field (name "Manufacturer") "UNI-ROYAL(厚声)")
      )
      (libsource (lib "easyedapro") (part "0402WGF5101TCE"))
    )
    (comp (ref "R2")
      (value "5.1kΩ")
      (footprint "easyedapro:R0402")
      (description "阻值:5.1kΩ;精度:±1%;功率:62.5mW;温度系数:±100ppm/°C;电阻类型:厚膜电阻;")
      (fields
        (field (name "Manufacturer Part") "0402WGF5101TCE")
        (field (name "Manufacturer") "UNI-ROYAL(厚声)")
      )
      (libsource (lib "easyedapro") (part "0402WGF5101TCE"))
    )
    (comp (ref "R11")
      (value "1kΩ")
      (footprint "easyedapro:R0402")
      (description "阻值:1kΩ;精度:±1%;功率:62.5mW;温度系数:±100ppm/°C;电阻类型:厚膜电阻;")
      (fields
        (field (name "Manufacturer Part") "0402WGF1001TCE")
        (field (name "Manufacturer") "UNI-ROYAL(厚声)")
      )
      (libsource (lib "easyedapro") (part "0402WGF1001TCE"))
    )
    (comp (ref "R12")
      (value "68kΩ")
      (footprint "easyedapro:R0402")
      (description "阻值:68kΩ;精度:±1%;功率:62.5mW;温度系数:±100ppm/°C;电阻类型:厚膜电阻;")
      (fields
        (field (name "Manufacturer Part") "0402WGF6802TCE")
        (field (name "Manufacturer") "UNI-ROYAL(厚声)")
      )
      (libsource (lib "easyedapro") (part "0402WGF6802TCE"))
    )
    (comp (ref "R13")
      (value "15kΩ")
      (footprint "easyedapro:R0402")
      (description "阻值:15kΩ;精度:±1%;功率:62.5mW;温度系数:±100ppm/°C;电阻类型:厚膜电阻;")
      (fields
        (field (name "Manufacturer Part") "0402WGF1502TCE")
        (field (name "Manufacturer") "UNI-ROYAL(厚声)")
      )
      (libsource (lib "easyedapro") (part "0402WGF1502TCE"))
    )
    (comp (ref "R18")
      (value "100kΩ")
      (footprint "easyedapro:R0402")
      (description "电阻类型:厚膜电阻;阻值:100kΩ;精度:±1%;功率:62.5mW;")
      (fields (field (name "Manufacturer Part") "RC0402FR-07100KL") (field (name "Manufacturer") "YAGEO(国巨)"))
      (libsource (lib "easyedapro") (part "RC0402FR-07100KL"))
    )
    (comp (ref "R19")
      (value "10.7kΩ")
      (footprint "easyedapro:R0402")
      (description "电阻类型:厚膜电阻;阻值:10.7kΩ;精度:±0.5%;功率:62.5mW;最大工作电压:50V;温度系数:±100ppm/°C;")
      (fields (field (name "Manufacturer Part") "AC0402DR-0710K7L") (field (name "Manufacturer") "YAGEO(国巨)"))
      (libsource (lib "easyedapro") (part "AC0402DR-0710K7L"))
    )
    (comp (ref "R20")
      (value "56kΩ")
      (footprint "easyedapro:R0402")
      (description "电阻类型:厚膜电阻;阻值:56kΩ;精度:±1%;功率:62.5mW;最大工作电压:50V;温度系数:±100ppm/°C;")
      (fields
        (field (name "Manufacturer Part") "0402WGF5602TCE")
        (field (name "Manufacturer") "UNI-ROYAL(厚声)")
      )
      (libsource (lib "easyedapro") (part "0402WGF5602TCE"))
    )
    (comp (ref "U3")
      (value "SY8089AAAC")
      (footprint "easyedapro:SOT-23-5_L3.0-W1.7-P0.95-LS2.8-BR")
      (description "功能类型:降压型;同步整流:-;输出通道数:-;拓扑结构:-;输入电压:-;输出电流(最大值):-;开关频率:-;")
      (fields (field (name "Manufacturer") "silergy(矽力杰)"))
      (libsource (lib "easyedapro") (part "SY8089AAAC"))
    )
    (comp (ref "U4")
      (value "CH340N")
      (footprint "easyedapro:SOP-8_L4.9-W3.9-P1.27-LS6.0-BL")
      (fields (field (name "Manufacturer") "WCH(南京沁恒)"))
      (libsource (lib "easyedapro") (part "CH340N_C2977777"))
    )
    (comp (ref "U5")
      (value "LGS5148")
      (footprint "easyedapro:SOT-23-6_L2.9-W1.6-P0.95-LS2.8-BL")
      (description "功能类型:降压型;输出类型:可调;输入电压:4.5V~48V;输出电压:800mV~48V;输出电流(最大值):600mA;")
      (fields (field (name "Manufacturer") "Legend-Si(棱晶半导体)"))
      (libsource (lib "easyedapro") (part "LGS5148"))
    )
    (comp (ref "USB1")
      (value "TYPE-C 16PIN 2MD(073)")
      (footprint "easyedapro:USB-C-SMD_TYPE-C-6PIN-2MD-073")
      (description "连接器类型:Type-C;标准:-;公母:母;端口数量:1;触点数量:16P;安装方式:卧贴;额定电流 - 电源:5A;工作温度范围:-25°C~+85°C;")
      (fields (field (name "Manufacturer") "SHOU HAN(首韩)"))
      (libsource (lib "easyedapro") (part "TYPE-C 16PIN 2MD(073)"))
    )
    (comp (ref "BT1")
      (value "CR1220-2ZX")
      (footprint "easyedapro:BAT-SMD_CR1220-2ZX")
      (description "连接器类型:电池底座;适用电池规格:CR1220;工作温度范围:-25°C~+85°C;")
      (fields (field (name "Manufacturer") "Q&J"))
      (libsource (lib "easyedapro") (part "CR1220-2ZX"))
    )
    (comp (ref "C1")
      (value "12pF")
      (footprint "easyedapro:C0402")
      (description "容值:12pF;精度:±5%;额定电压:50V;材质(温度系数):C0G;")
      (fields (field (name "Manufacturer Part") "FN15N120J500PNG") (field (name "Manufacturer") "PSA(信昌电陶)"))
      (libsource (lib "easyedapro") (part "FN15N120J500PNG"))
    )
    (comp (ref "C2")
      (value "12pF")
      (footprint "easyedapro:C0402")
      (description "容值:12pF;精度:±5%;额定电压:50V;材质(温度系数):C0G;")
      (fields (field (name "Manufacturer Part") "FN15N120J500PNG") (field (name "Manufacturer") "PSA(信昌电陶)"))
      (libsource (lib "easyedapro") (part "FN15N120J500PNG"))
    )
    (comp (ref "U2")
      (value "DS1307M/TR")
      (footprint "easyedapro:SOP-8_L4.9-W3.9-P1.27-LS6.0-BL")
      (fields (field (name "Manufacturer") "HGSEMI(华冠)"))
      (libsource (lib "easyedapro") (part "DS1307M/TR"))
    )
    (comp (ref "X1")
      (value "32.768kHz")
      (footprint "easyedapro:OSC-TH_BD3.1-P0.8-D0.3")
      (description "晶振类型:直插晶振;频率:32.768kHz;常温频差:±20ppm;外接负载电容:12.5pF;")
      (fields
        (field (name "Manufacturer Part") "TAXD32768K2CGDAZT2T")
        (field (name "Manufacturer") "YJX(雅晶鑫)")
      )
      (libsource (lib "easyedapro") (part "TDXLF-308 32.768KHZ 12.5PF 20PPM"))
    )
    (comp (ref "USB2")
      (value "U-USBAR04P-F002")
      (footprint "easyedapro:USB-A-TH_USB-302-T")
      (description "连接器类型:Type-A;标准:USB 2.0;公母:母;端口数量:1;触点数量:4P;安装方式:弯插;额定电流 - 电源:1.5A;工作温度范围:0°C~+50°C;")
      (fields (field (name "Manufacturer") "Ckmtw(灿科盟)"))
      (libsource (lib "easyedapro") (part "U-USBAR04P-F001"))
    )
    (comp (ref "C9")
      (value "10uF")
      (footprint "easyedapro:C0402")
      (description "容值:10uF;精度:±20%;额定电压:6.3V;材质(温度系数):X5R;")
      (fields
        (field (name "Manufacturer Part") "CL05A106MQ5NUNC")
        (field (name "Manufacturer") "SAMSUNG(三星)")
      )
      (libsource (lib "easyedapro") (part "CL05A106MQ5NUNC"))
    )
    (comp (ref "C28")
      (value "10uF")
      (footprint "easyedapro:C0402")
      (description "容值:10uF;精度:±20%;额定电压:6.3V;材质(温度系数):X5R;")
      (fields
        (field (name "Manufacturer Part") "CL05A106MQ5NUNC")
        (field (name "Manufacturer") "SAMSUNG(三星)")
      )
      (libsource (lib "easyedapro") (part "CL05A106MQ5NUNC"))
    )
    (comp (ref "C29")
      (value "10uF")
      (footprint "easyedapro:C0402")
      (description "容值:10uF;精度:±20%;额定电压:6.3V;材质(温度系数):X5R;")
      (fields
        (field (name "Manufacturer Part") "CL05A106MQ5NUNC")
        (field (name "Manufacturer") "SAMSUNG(三星)")
      )
      (libsource (lib "easyedapro") (part "CL05A106MQ5NUNC"))
    )
    (comp (ref "C30")
      (value "10uF")
      (footprint "easyedapro:C0402")
      (description "容值:10uF;精度:±20%;额定电压:6.3V;材质(温度系数):X5R;")
      (fields
        (field (name "Manufacturer Part") "CL05A106MQ5NUNC")
        (field (name "Manufacturer") "SAMSUNG(三星)")
      )
      (libsource (lib "easyedapro") (part "CL05A106MQ5NUNC"))
    )
    (comp (ref "C31")
      (value "10uF")
      (footprint "easyedapro:C0402")
      (description "容值:10uF;精度:±20%;额定电压:6.3V;材质(温度系数):X5R;")
      (fields
        (field (name "Manufacturer Part") "CL05A106MQ5NUNC")
        (field (name "Manufacturer") "SAMSUNG(三星)")
      )
      (libsource (lib "easyedapro") (part "CL05A106MQ5NUNC"))
    )
    (comp (ref "C32")
      (value "10uF")
      (footprint "easyedapro:C0402")
      (description "容值:10uF;精度:±20%;额定电压:6.3V;材质(温度系数):X5R;")
      (fields
        (field (name "Manufacturer Part") "CL05A106MQ5NUNC")
        (field (name "Manufacturer") "SAMSUNG(三星)")
      )
      (libsource (lib "easyedapro") (part "CL05A106MQ5NUNC"))
    )
    (comp (ref "D2")
      (value "MB10S")
      (footprint "easyedapro:MBS_L4.7-W3.8-P2.40-LS7.0-TL")
      (description "正向压降(Vf):1.1V@400mA;直流反向耐压(Vr):1kV;平均整流电流(Io):1A;正向浪涌电流(Ifsm):35A;")
      (fields (field (name "Manufacturer") "MDD"))
      (libsource (lib "easyedapro") (part "MB10S_C2488"))
    )
    (comp (ref "D3")
      (value "MB10S")
      (footprint "easyedapro:MBS_L4.7-W3.8-P2.40-LS7.0-TL")
      (description "正向压降(Vf):1.1V@400mA;直流反向耐压(Vr):1kV;平均整流电流(Io):1A;正向浪涌电流(Ifsm):35A;")
      (fields (field (name "Manufacturer") "MDD"))
      (libsource (lib "easyedapro") (part "MB10S_C2488"))
    )
    (comp (ref "D4")
      (value "MB10S")
      (footprint "easyedapro:MBS_L4.7-W3.8-P2.40-LS7.0-TL")
      (description "正向压降(Vf):1.1V@400mA;直流反向耐压(Vr):1kV;平均整流电流(Io):1A;正向浪涌电流(Ifsm):35A;")
      (fields (field (name "Manufacturer") "MDD"))
      (libsource (lib "easyedapro") (part "MB10S_C2488"))
    )
    (comp (ref "D5")
      (value "MB10S")
      (footprint "easyedapro:MBS_L4.7-W3.8-P2.40-LS7.0-TL")
      (description "正向压降(Vf):1.1V@400mA;直流反向耐压(Vr):1kV;平均整流电流(Io):1A;正向浪涌电流(Ifsm):35A;")
      (fields (field (name "Manufacturer") "MDD"))
      (libsource (lib "easyedapro") (part "MB10S_C2488"))
    )
    (comp (ref "R7")
      (value "24.9kΩ")
      (footprint "easyedapro:R0402")
      (description "电阻类型:厚膜电阻;阻值:24.9kΩ;精度:±1%;功率:100mW;最大工作电压:-;温度系数:±100ppm/°C;")
      (fields (field (name "Manufacturer Part") "ERJ2RKF2492X") (field (name "Manufacturer") "PANASONIC(松下)"))
      (libsource (lib "easyedapro") (part "ERJ2RKF2492X"))
    )
    (comp (ref "R8")
      (value "33kΩ")
      (footprint "easyedapro:R0402")
      (description "阻值:33kΩ;精度:±1%;功率:62.5mW;温度系数:±100ppm/°C;电阻类型:厚膜电阻;")
      (fields
        (field (name "Manufacturer Part") "0402WGF3302TCE")
        (field (name "Manufacturer") "UNI-ROYAL(厚声)")
      )
      (libsource (lib "easyedapro") (part "0402WGF3302TCE"))
    )
    (comp (ref "R9")
      (value "200kΩ")
      (footprint "easyedapro:R0402")
      (description "电阻类型:厚膜电阻;阻值:200kΩ;精度:±1%;功率:62.5mW;最大工作电压:50V;温度系数:±100ppm/°C;")
      (fields
        (field (name "Manufacturer Part") "0402WGF2003TCE")
        (field (name "Manufacturer") "UNI-ROYAL(厚声)")
      )
      (libsource (lib "easyedapro") (part "0402WGF2003TCE"))
    )
    (comp (ref "RJ1")
      (value "R-RJ45R08P-C000")
      (footprint "easyedapro:RJ45-TH_R-RJ45R08P-C000")
      (description "连接器类型:RJ插座;USOC代码:RJ45;端口数量:1;等级:-;安装方式:弯插;屏蔽:有屏蔽;LED:带LED;工作温度范围:0°C~+70°C;")
      (fields (field (name "Manufacturer") "Ckmtw(灿科盟)"))
      (libsource (lib "easyedapro") (part "R-RJ45R08P-C000"))
    )
    (comp (ref "RJ2")
      (value "R-RJ45R08P-C000")
      (footprint "easyedapro:RJ45-TH_R-RJ45R08P-C000")
      (description "连接器类型:RJ插座;USOC代码:RJ45;端口数量:1;等级:-;安装方式:弯插;屏蔽:有屏蔽;LED:带LED;工作温度范围:0°C~+70°C;")
      (fields (field (name "Manufacturer") "Ckmtw(灿科盟)"))
      (libsource (lib "easyedapro") (part "R-RJ45R08P-C000"))
    )
    (comp (ref "U6")
      (value "G2415S")
      (footprint "easyedapro:SMD-24_L15.1-W7.1-P1.00-LS10.0-BL")
      (description "端口:单口;功能(POE或非POE):POE;线圈组数:4;速率:1000M;")
      (fields (field (name "Manufacturer") "CND-tek(磁联达)"))
      (libsource (lib "easyedapro") (part "G2415S"))
    )
    (comp (ref "U7")
      (value "XS2100S")
      (footprint "easyedapro:SOP-8_L4.9-W3.9-P1.27-LS6.0-BL")
      (fields (field (name "Manufacturer") "chipup(芯昇)"))
      (libsource (lib "easyedapro") (part "XS2100S"))
    )
    (comp (ref "U8")
      (value "G2415S")
      (footprint "easyedapro:SMD-24_L15.1-W7.1-P1.00-LS10.0-BL")
      (description "端口:单口;功能(POE或非POE):POE;线圈组数:4;速率:1000M;")
      (fields (field (name "Manufacturer") "CND-tek(磁联达)"))
      (libsource (lib "easyedapro") (part "G2415S"))
    )
    (comp (ref "U9")
      (value "1.27kΩ")
      (footprint "easyedapro:R0402")
      (description "电阻类型:厚膜电阻;阻值:1.27kΩ;精度:±1%;功率:62.5mW;最大工作电压:50V;温度系数:±100ppm/°C;")
      (fields (field (name "Manufacturer Part") "FRC0402F1271TS") (field (name "Manufacturer") "FOJAN(富捷)"))
      (libsource (lib "easyedapro") (part "FRC0402F1271TS"))
    )
    (comp (ref "CN3")
      (value "PH-2A")
      (footprint "easyedapro:CONN-TH_PH-2A_C2908623")
      (fields (field (name "Manufacturer") "HCTL(华灿天禄)"))
      (libsource (lib "easyedapro") (part "PH-2A_C2908623"))
    )
    (comp (ref "U12")
      (value "HC-PHB2.0-2x4A")
      (footprint "easyedapro:CONN-TH_8P-P2.00_HC-PHB2.0-2X4A")
      (fields (field (name "Manufacturer") "HC(虹成电子)"))
      (libsource (lib "easyedapro") (part "HC-PHB2.0-2X4A"))
    )
  )
  (nets
    (net (code "1") (name "3V3") (class "Default")
      (node (ref "C16") (pin "2") (pinfunction "2_2") (pintype "input"))
      (node (ref "C17") (pin "2") (pinfunction "2_2") (pintype "unspecified"))
      (node (ref "CN2") (pin "2") (pinfunction "2_2") (pintype "unspecified"))
      (node (ref "L1") (pin "2") (pinfunction "2_2") (pintype "input"))
      (node (ref "R12") (pin "1") (pinfunction "1_1") (pintype "input"))
      (node (ref "R14") (pin "1") (pinfunction "1_1") (pintype "input"))
      (node (ref "R15") (pin "2") (pinfunction "2_2") (pintype "input"))
      (node (ref "R23") (pin "1") (pinfunction "1_1") (pintype "input"))
      (node (ref "R5") (pin "1") (pinfunction "1_1") (pintype "input"))
      (node (ref "R6") (pin "1") (pinfunction "1_1") (pintype "input"))
      (node (ref "RJ1") (pin "11") (pinfunction "R+_11") (pintype "unspecified"))
      (node (ref "RJ1") (pin "9") (pinfunction "L+_9") (pintype "unspecified"))
      (node (ref "RJ2") (pin "11") (pinfunction "R+_11") (pintype "unspecified"))
      (node (ref "RJ2") (pin "9") (pinfunction "L+_9") (pintype "unspecified"))
      (node (ref "U1") (pin "2") (pinfunction "3.3VD_2") (pintype "unspecified"))
      (node (ref "U1") (pin "3") (pinfunction "3.3VD_3") (pintype "unspecified"))
      (node (ref "U12") (pin "2") (pinfunction "2_2") (pintype "unspecified"))
    )
    (net (code "2") (name "5V") (class "Default")
      (node (ref "C15") (pin "2") (pinfunction "2_2") (pintype "input"))
      (node (ref "C20") (pin "1") (pinfunction "1_1") (pintype "input"))
      (node (ref "C21") (pin "1") (pinfunction "1_1") (pintype "input"))
      (node (ref "C22") (pin "1") (pinfunction "1_1") (pintype "input"))
      (node (ref "C23") (pin "1") (pinfunction "1_1") (pintype "input"))
      (node (ref "L2") (pin "2") (pinfunction "2_2") (pintype "unspecified"))
      (node (ref "R11") (pin "2") (pinfunction "2_2") (pintype "input"))
      (node (ref "R20") (pin "2") (pinfunction "2_2") (pintype "input"))
      (node (ref "U2") (pin "8") (pinfunction "VCC_8") (pintype "unspecified"))
      (node (ref "U3") (pin "4") (pinfunction "IN_4") (pintype "input"))
      (node (ref "U4") (pin "5") (pinfunction "VCC_5") (pintype "unspecified"))
      (node (ref "USB1") (pin "11") (pinfunction "VBUS_11") (pintype "unspecified"))
      (node (ref "USB1") (pin "2") (pinfunction "VBUS_2") (pintype "unspecified"))
      (node (ref "USB2") (pin "1") (pinfunction "VCC_1") (pintype "unspecified"))
    )
    (net (code "3") (name "CONSOLE-RX") (class "Default")
      (node (ref "R3") (pin "1") (pinfunction "1_1") (pintype "input"))
      (node (ref "U1") (pin "32") (pinfunction "UART_RXD0_32") (pintype "unspecified"))
    )
    (net (code "4") (name "CONSOLE-TX") (class "Default")
      (node (ref "R4") (pin "1") (pinfunction "1_1") (pintype "input"))
      (node (ref "U1") (pin "31") (pinfunction "UART_TXD0_31") (pintype "unspecified"))
    )
    (net (code "5") (name "DEBUG-RX") (class "Default")
      (node (ref "R4") (pin "2") (pinfunction "2_2") (pintype "input"))
      (node (ref "U4") (pin "7") (pinfunction "RXD_7") (pintype "unspecified"))
    )
    (net (code "6") (name "DEBUG-TX") (class "Default")
      (node (ref "R3") (pin "2") (pinfunction "2_2") (pintype "input"))
      (node (ref "U4") (pin "6") (pinfunction "TXD_6") (pintype "unspecified"))
    )
    (net (code "7") (name "DM-UP") (class "Default")
      (node (ref "U4") (pin "2") (pinfunction "UD-_2") (pintype "unspecified"))
      (node (ref "USB1") (pin "5") (pinfunction "DN2_5") (pintype "unspecified"))
      (node (ref "USB1") (pin "7") (pinfunction "DN1_7") (pintype "unspecified"))
    )
    (net (code "8") (name "DP-UP") (class "Default")
      (node (ref "U4") (pin "1") (pinfunction "UD+_1") (pintype "unspecified"))
      (node (ref "USB1") (pin "6") (pinfunction "DP1_6") (pintype "unspecified"))
      (node (ref "USB1") (pin "8") (pinfunction "DP2_8") (pintype "unspecified"))
    )
    (net (code "9") (name "ETH-LED0") (class "Default")
      (node (ref "R21") (pin "2") (pinfunction "2_2") (pintype "input"))
      (node (ref "U1") (pin "13") (pinfunction "EPHY_LED0_13") (pintype "unspecified"))
    )
    (net (code "10") (name "ETH-LED1") (class "Default")
      (node (ref "R22") (pin "2") (pinfunction "2_2") (pintype "input"))
      (node (ref "U1") (pin "12") (pinfunction "EPHY_LED1_12") (pintype "unspecified"))
    )
    (net (code "11") (name "ETH-LED2") (class "Default")
      (node (ref "U1") (pin "11") (pinfunction "EPHY_LED2_11") (pintype "unspecified"))
    )
    (net (code "12") (name "ETH-LED3") (class "Default")
      (node (ref "U1") (pin "10") (pinfunction "EPHY_LED3_10") (pintype "unspecified"))
    )
    (net (code "13") (name "ETH-LED4") (class "Default")
      (node (ref "U1") (pin "9") (pinfunction "EPHY_LED4_9") (pintype "unspecified"))
    )
    (net (code "14") (name "ETH-RN0") (class "Default")
      (node (ref "U1") (pin "35") (pinfunction "MDI_RN_P0_35") (pintype "unspecified"))
      (node (ref "U6") (pin "6") (pinfunction "TD2-_6") (pintype "unspecified"))
    )
    (net (code "15") (name "ETH-RN1") (class "Default")
      (node (ref "U1") (pin "41") (pinfunction "MDI_RN_P1_41") (pintype "unspecified"))
      (node (ref "U8") (pin "6") (pinfunction "TD2-_6") (pintype "unspecified"))
    )
    (net (code "16") (name "ETH-RN2") (class "Default")
      (node (ref "U1") (pin "43") (pinfunction "MDI_RN_P2_43") (pintype "unspecified"))
    )
    (net (code "17") (name "ETH-RN3") (class "Default")
      (node (ref "U1") (pin "49") (pinfunction "MDI_RN_P3_49") (pintype "unspecified"))
    )
    (net (code "18") (name "ETH-RN4") (class "Default")
      (node (ref "U1") (pin "51") (pinfunction "MDI_RN_P4_51") (pintype "unspecified"))
    )
    (net (code "19") (name "ETH-RP0") (class "Default")
      (node (ref "U1") (pin "34") (pinfunction "MDI_RP_P0_34") (pintype "unspecified"))
      (node (ref "U6") (pin "5") (pinfunction "TD2+_5") (pintype "unspecified"))
    )
    (net (code "20") (name "ETH-RP1") (class "Default")
      (node (ref "U1") (pin "40") (pinfunction "MDI_RP_P1_40") (pintype "unspecified"))
      (node (ref "U8") (pin "5") (pinfunction "TD2+_5") (pintype "unspecified"))
    )
    (net (code "21") (name "ETH-RP2") (class "Default")
      (node (ref "U1") (pin "42") (pinfunction "MDI_RP_P2_42") (pintype "unspecified"))
    )
    (net (code "22") (name "ETH-RP3") (class "Default")
      (node (ref "U1") (pin "48") (pinfunction "MDI_RP_P3_48") (pintype "unspecified"))
    )
    (net (code "23") (name "ETH-RP4") (class "Default")
      (node (ref "U1") (pin "50") (pinfunction "MDI_RP_P4_50") (pintype "unspecified"))
    )
    (net (code "24") (name "ETH-TN0") (class "Default")
      (node (ref "U1") (pin "37") (pinfunction "MDI_TN_P0_37") (pintype "unspecified"))
      (node (ref "U6") (pin "3") (pinfunction "TD1-_3") (pintype "unspecified"))
    )
    (net (code "25") (name "ETH-TN1") (class "Default")
      (node (ref "U1") (pin "39") (pinfunction "MDI_TN_P1_39") (pintype "unspecified"))
      (node (ref "U8") (pin "3") (pinfunction "TD1-_3") (pintype "unspecified"))
    )
    (net (code "26") (name "ETH-TN2") (class "Default")
      (node (ref "U1") (pin "45") (pinfunction "MDI_TN_P2_45") (pintype "unspecified"))
    )
    (net (code "27") (name "ETH-TN3") (class "Default")
      (node (ref "U1") (pin "47") (pinfunction "MDI_TN_P3_47") (pintype "unspecified"))
    )
    (net (code "28") (name "ETH-TN4") (class "Default")
      (node (ref "U1") (pin "53") (pinfunction "MDI_TN_P4_53") (pintype "unspecified"))
    )
    (net (code "29") (name "ETH-TP0") (class "Default")
      (node (ref "U1") (pin "36") (pinfunction "MDI_TP_P0_36") (pintype "unspecified"))
      (node (ref "U6") (pin "2") (pinfunction "TD1+_2") (pintype "unspecified"))
    )
    (net (code "30") (name "ETH-TP1") (class "Default")
      (node (ref "U1") (pin "38") (pinfunction "MDI_TP_P1_38") (pintype "unspecified"))
      (node (ref "U8") (pin "2") (pinfunction "TD1+_2") (pintype "unspecified"))
    )
    (net (code "31") (name "ETH-TP2") (class "Default")
      (node (ref "U1") (pin "44") (pinfunction "MDI_TP_P2_44") (pintype "unspecified"))
    )
    (net (code "32") (name "ETH-TP3") (class "Default")
      (node (ref "U1") (pin "46") (pinfunction "MDI_TP_P3_46") (pintype "unspecified"))
    )
    (net (code "33") (name "ETH-TP4") (class "Default")
      (node (ref "U1") (pin "52") (pinfunction "MDI_TP_P4_52") (pintype "unspecified"))
    )
    (net (code "34") (name "GND") (class "Default")
      (node (ref "BT1") (pin "2") (pinfunction "2_2") (pintype "input"))
      (node (ref "C1") (pin "2") (pinfunction "2_2") (pintype "unspecified"))
      (node (ref "C15") (pin "1") (pinfunction "1_1") (pintype "input"))
      (node (ref "C16") (pin "1") (pinfunction "1_1") (pintype "input"))
      (node (ref "C17") (pin "1") (pinfunction "1_1") (pintype "unspecified"))
      (node (ref "C18") (pin "2") (pinfunction "2_2") (pintype "unspecified"))
      (node (ref "C19") (pin "1") (pinfunction "1_1") (pintype "input"))
      (node (ref "C2") (pin "2") (pinfunction "2_2") (pintype "unspecified"))
      (node (ref "C20") (pin "2") (pinfunction "2_2") (pintype "input"))
      (node (ref "C21") (pin "2") (pinfunction "2_2") (pintype "input"))
      (node (ref "C22") (pin "2") (pinfunction "2_2") (pintype "input"))
      (node (ref "C23") (pin "2") (pinfunction "2_2") (pintype "input"))
      (node (ref "C24") (pin "1") (pinfunction "1_1") (pintype "unspecified"))
      (node (ref "C25") (pin "2") (pinfunction "2_2") (pintype "input"))
      (node (ref "C26") (pin "1") (pinfunction "1_1") (pintype "unspecified"))
      (node (ref "C28") (pin "1") (pinfunction "1_1") (pintype "input"))
      (node (ref "C29") (pin "1") (pinfunction "1_1") (pintype "input"))
      (node (ref "C30") (pin "1") (pinfunction "1_1") (pintype "input"))
      (node (ref "C31") (pin "1") (pinfunction "1_1") (pintype "input"))
      (node (ref "C32") (pin "1") (pinfunction "1_1") (pintype "input"))
      (node (ref "C9") (pin "1") (pinfunction "1_1") (pintype "input"))
      (node (ref "CN2") (pin "1") (pinfunction "1_1") (pintype "unspecified"))
      (node (ref "CN2") (pin "7") (pinfunction "7_7") (pintype "unspecified"))
      (node (ref "CN3") (pin "1") (pinfunction "1_1") (pintype "unspecified"))
      (node (ref "D1") (pin "2") (pinfunction "-_2") (pintype "unspecified"))
      (node (ref "R1") (pin "2") (pinfunction "2_2") (pintype "input"))
      (node (ref "R13") (pin "2") (pinfunction "2_2") (pintype "input"))
      (node (ref "R19") (pin "1") (pinfunction "1_1") (pintype "unspecified"))
      (node (ref "R2") (pin "2") (pinfunction "2_2") (pintype "input"))
      (node (ref "RJ1") (pin "13") (pinfunction "S_13") (pintype "unspecified"))
      (node (ref "RJ1") (pin "14") (pinfunction "S_14") (pintype "unspecified"))
      (node (ref "RJ2") (pin "13") (pinfunction "S_13") (pintype "unspecified"))
      (node (ref "RJ2") (pin "14") (pinfunction "S_14") (pintype "unspecified"))
      (node (ref "SW1") (pin "2") (pinfunction "2_2") (pintype "input"))
      (node (ref "SW1") (pin "3") (pinfunction "3_3") (pintype "input"))
      (node (ref "SW1") (pin "4") (pinfunction "4_4") (pintype "input"))
      (node (ref "U1") (pin "1") (pinfunction "GND_1") (pintype "unspecified"))
      (node (ref "U1") (pin "21") (pinfunction "GND_21") (pintype "unspecified"))
      (node (ref "U1") (pin "23") (pinfunction "GND_23") (pintype "unspecified"))
      (node (ref "U1") (pin "4") (pinfunction "GND_4") (pintype "unspecified"))
      (node (ref "U1") (pin "56") (pinfunction "GND_56") (pintype "unspecified"))
      (node (ref "U1") (pin "57") (pinfunction "GND_57") (pintype "unspecified"))
      (node (ref "U1") (pin "58") (pinfunction "GND_58") (pintype "unspecified"))
      (node (ref "U1") (pin "59") (pinfunction "GND_59") (pintype "unspecified"))
      (node (ref "U12") (pin "1") (pinfunction "1_1") (pintype "unspecified"))
      (node (ref "U2") (pin "4") (pinfunction "GND_4") (pintype "unspecified"))
      (node (ref "U3") (pin "2") (pinfunction "GND_2") (pintype "input"))
      (node (ref "U4") (pin "3") (pinfunction "GND_3") (pintype "unspecified"))
      (node (ref "U5") (pin "2") (pinfunction "GND_2") (pintype "input"))
      (node (ref "U7") (pin "5") (pinfunction "RTN_5") (pintype "input"))
      (node (ref "U7") (pin "8") (pinfunction "WAD_8") (pintype "input"))
      (node (ref "USB1") (pin "1") (pinfunction "GND_1") (pintype "unspecified"))
      (node (ref "USB1") (pin "12") (pinfunction "GND_12") (pintype "unspecified"))
      (node (ref "USB1") (pin "13") (pinfunction "SHELL_13") (pintype "unspecified"))
      (node (ref "USB1") (pin "14") (pinfunction "SHELL_14") (pintype "unspecified"))
      (node (ref "USB2") (pin "4") (pinfunction "GND_4") (pintype "unspecified"))
      (node (ref "USB2") (pin "5") (pinfunction "SH1_5") (pintype "unspecified"))
      (node (ref "USB2") (pin "6") (pinfunction "SH2_6") (pintype "unspecified"))
    )
    (net (code "35") (name "GND_POE") (class "Default")
      (node (ref "D2") (pin "2") (pinfunction "-_2") (pintype "unspecified"))
      (node (ref "D3") (pin "2") (pinfunction "-_2") (pintype "unspecified"))
      (node (ref "D4") (pin "2") (pinfunction "-_2") (pintype "unspecified"))
      (node (ref "D5") (pin "2") (pinfunction "-_2") (pintype "unspecified"))
      (node (ref "U7") (pin "4") (pinfunction "VSS_4") (pintype "input"))
      (node (ref "U9") (pin "1") (pinfunction "1_1") (pintype "unspecified"))
    )
    (net (code "36") (name "GPIO0") (class "Default")
      (node (ref "CN2") (pin "12") (pinfunction "12_12") (pintype "unspecified"))
      (node (ref "U1") (pin "30") (pinfunction "GPIO0_30") (pintype "unspecified"))
    )
    (net (code "37") (name "I2C-SCK") (class "Default")
      (node (ref "CN2") (pin "3") (pinfunction "3_3") (pintype "unspecified"))
      (node (ref "R5") (pin "2") (pinfunction "2_2") (pintype "input"))
      (node (ref "U1") (pin "24") (pinfunction "I2C_SCLK_24") (pintype "unspecified"))
      (node (ref "U12") (pin "3") (pinfunction "3_3") (pintype "unspecified"))
      (node (ref "U2") (pin "6") (pinfunction "SCL_6") (pintype "unspecified"))
    )
    (net (code "38") (name "I2C-SDA") (class "Default")
      (node (ref "CN2") (pin "4") (pinfunction "4_4") (pintype "unspecified"))
      (node (ref "R6") (pin "2") (pinfunction "2_2") (pintype "input"))
      (node (ref "U1") (pin "25") (pinfunction "I2C_SD_25") (pintype "unspecified"))
      (node (ref "U12") (pin "4") (pinfunction "4_4") (pintype "unspecified"))
      (node (ref "U2") (pin "5") (pinfunction "SDA_5") (pintype "unspecified"))
    )
    (net (code "39") (name "I2S-CLK") (class "Default")
      (node (ref "U1") (pin "20") (pinfunction "I2S_CLK_20") (pintype "unspecified"))
      (node (ref "U12") (pin "8") (pinfunction "8_8") (pintype "unspecified"))
    )
    (net (code "40") (name "I2S-SDI") (class "Default")
      (node (ref "U1") (pin "17") (pinfunction "I2S_SDI_17") (pintype "unspecified"))
      (node (ref "U12") (pin "5") (pinfunction "5_5") (pintype "unspecified"))
    )
    (net (code "41") (name "I2S-SDO") (class "Default")
      (node (ref "U1") (pin "18") (pinfunction "I2S_SDO_18") (pintype "unspecified"))
      (node (ref "U12") (pin "6") (pinfunction "6_6") (pintype "unspecified"))
    )
    (net (code "42") (name "I2S-WS") (class "Default")
      (node (ref "U1") (pin "19") (pinfunction "I2S_WS_19") (pintype "unspecified"))
      (node (ref "U12") (pin "7") (pinfunction "7_7") (pintype "unspecified"))
    )
    (net (code "43") (name "KEY-RESTART") (class "Default")
      (node (ref "C26") (pin "2") (pinfunction "2_2") (pintype "unspecified"))
      (node (ref "R14") (pin "2") (pinfunction "2_2") (pintype "input"))
      (node (ref "SW1") (pin "1") (pinfunction "1_1") (pintype "input"))
      (node (ref "U1") (pin "8") (pinfunction "WDT_RST_N_8") (pintype "unspecified"))
    )
    (net (code "44") (name "Net-(D1-C1)") (class "Default")
      (node (ref "CN1") (pin "1") (pinfunction "1_1") (pintype "unspecified"))
      (node (ref "D1") (pin "4") (pinfunction "C1_4") (pintype "unspecified"))
    )
    (net (code "45") (name "Net-(D1-C2)") (class "Default")
      (node (ref "CN1") (pin "2") (pinfunction "2_2") (pintype "unspecified"))
      (node (ref "D1") (pin "3") (pinfunction "C2_3") (pintype "unspecified"))
    )
    (net (code "46") (name "Net-(LED1-A)") (class "Default")
      (node (ref "LED1") (pin "2") (pinfunction "A_2") (pintype "input"))
      (node (ref "R15") (pin "1") (pinfunction "1_1") (pintype "input"))
    )
    (net (code "47") (name "Net-(U2-VBAT)") (class "Default")
      (node (ref "BT1") (pin "1") (pinfunction "1_1") (pintype "input"))
      (node (ref "U2") (pin "3") (pinfunction "VBAT_3") (pintype "unspecified"))
    )
    (net (code "48") (name "Net-(U2-X1)") (class "Default")
      (node (ref "C2") (pin "1") (pinfunction "1_1") (pintype "unspecified"))
      (node (ref "U2") (pin "1") (pinfunction "X1_1") (pintype "unspecified"))
      (node (ref "X1") (pin "2") (pinfunction "OSC2_2") (pintype "input"))
    )
    (net (code "49") (name "Net-(U2-X2)") (class "Default")
      (node (ref "C1") (pin "1") (pinfunction "1_1") (pintype "unspecified"))
      (node (ref "U2") (pin "2") (pinfunction "X2_2") (pintype "unspecified"))
      (node (ref "X1") (pin "1") (pinfunction "OSC1_1") (pintype "input"))
    )
    (net (code "50") (name "Net-(U3-EN)") (class "Default")
      (node (ref "R11") (pin "1") (pinfunction "1_1") (pintype "input"))
      (node (ref "U3") (pin "1") (pinfunction "EN_1") (pintype "input"))
    )
    (net (code "51") (name "Net-(U3-FB)") (class "Default")
      (node (ref "R12") (pin "2") (pinfunction "2_2") (pintype "input"))
      (node (ref "R13") (pin "1") (pinfunction "1_1") (pintype "input"))
      (node (ref "U3") (pin "5") (pinfunction "FB_5") (pintype "input"))
    )
    (net (code "52") (name "Net-(U3-LX)") (class "Default")
      (node (ref "L1") (pin "1") (pinfunction "1_1") (pintype "input"))
      (node (ref "U3") (pin "3") (pinfunction "LX_3") (pintype "input"))
    )
    (net (code "53") (name "Net-(U4-V3)") (class "Default")
      (node (ref "C24") (pin "2") (pinfunction "2_2") (pintype "unspecified"))
      (node (ref "C25") (pin "1") (pinfunction "1_1") (pintype "input"))
      (node (ref "U4") (pin "8") (pinfunction "V3_8") (pintype "unspecified"))
    )
    (net (code "54") (name "Net-(U5-BST)") (class "Default")
      (node (ref "C27") (pin "2") (pinfunction "2_2") (pintype "unspecified"))
      (node (ref "U5") (pin "1") (pinfunction "BST_1") (pintype "input"))
    )
    (net (code "55") (name "Net-(U5-EN)") (class "Default")
      (node (ref "R18") (pin "1") (pinfunction "1_1") (pintype "input"))
      (node (ref "U5") (pin "4") (pinfunction "EN_4") (pintype "input"))
    )
    (net (code "56") (name "Net-(U5-FB)") (class "Default")
      (node (ref "R19") (pin "2") (pinfunction "2_2") (pintype "unspecified"))
      (node (ref "R20") (pin "1") (pinfunction "1_1") (pintype "input"))
      (node (ref "U5") (pin "3") (pinfunction "FB_3") (pintype "input"))
    )
    (net (code "57") (name "Net-(U5-SW)") (class "Default")
      (node (ref "C27") (pin "1") (pinfunction "1_1") (pintype "unspecified"))
      (node (ref "L2") (pin "1") (pinfunction "1_1") (pintype "unspecified"))
      (node (ref "U5") (pin "6") (pinfunction "SW_6") (pintype "input"))
    )
    (net (code "58") (name "Net-(U6-MX1+)") (class "Default")
      (node (ref "RJ1") (pin "1") (pinfunction "1_1") (pintype "unspecified"))
      (node (ref "U6") (pin "23") (pinfunction "MX1+_23") (pintype "unspecified"))
    )
    (net (code "59") (name "Net-(U6-MX1-)") (class "Default")
      (node (ref "RJ1") (pin "2") (pinfunction "2_2") (pintype "unspecified"))
      (node (ref "U6") (pin "22") (pinfunction "MX1-_22") (pintype "unspecified"))
    )
    (net (code "60") (name "Net-(U6-MX2+)") (class "Default")
      (node (ref "RJ1") (pin "3") (pinfunction "3_3") (pintype "unspecified"))
      (node (ref "U6") (pin "20") (pinfunction "MX2+_20") (pintype "unspecified"))
    )
    (net (code "61") (name "Net-(U6-MX2-)") (class "Default")
      (node (ref "RJ1") (pin "6") (pinfunction "6_6") (pintype "unspecified"))
      (node (ref "U6") (pin "19") (pinfunction "MX2-_19") (pintype "unspecified"))
    )
    (net (code "62") (name "Net-(U6-MX4+)") (class "Default")
      (node (ref "RJ1") (pin "7") (pinfunction "7_7") (pintype "unspecified"))
      (node (ref "U6") (pin "14") (pinfunction "MX4+_14") (pintype "unspecified"))
    )
    (net (code "63") (name "Net-(U6-MX4-)") (class "Default")
      (node (ref "RJ1") (pin "8") (pinfunction "8_8") (pintype "unspecified"))
      (node (ref "U6") (pin "13") (pinfunction "MX4-_13") (pintype "unspecified"))
    )
    (net (code "64") (name "Net-(U6-MXT3+)") (class "Default")
      (node (ref "RJ1") (pin "4") (pinfunction "4_4") (pintype "unspecified"))
      (node (ref "U6") (pin "17") (pinfunction "MXT3+_17") (pintype "unspecified"))
    )
    (net (code "65") (name "Net-(U6-MXT3-)") (class "Default")
      (node (ref "RJ1") (pin "5") (pinfunction "5_5") (pintype "unspecified"))
      (node (ref "U6") (pin "16") (pinfunction "MXT3-_16") (pintype "unspecified"))
    )
    (net (code "66") (name "Net-(U6-TCT1)") (class "Default")
      (node (ref "C28") (pin "2") (pinfunction "2_2") (pintype "input"))
      (node (ref "C29") (pin "2") (pinfunction "2_2") (pintype "input"))
      (node (ref "C30") (pin "2") (pinfunction "2_2") (pintype "input"))
      (node (ref "C31") (pin "2") (pinfunction "2_2") (pintype "input"))
      (node (ref "C32") (pin "2") (pinfunction "2_2") (pintype "input"))
      (node (ref "C9") (pin "2") (pinfunction "2_2") (pintype "input"))
      (node (ref "U6") (pin "1") (pinfunction "TCT1_1") (pintype "unspecified"))
      (node (ref "U6") (pin "4") (pinfunction "TCT2_4") (pintype "unspecified"))
      (node (ref "U8") (pin "1") (pinfunction "TCT1_1") (pintype "unspecified"))
      (node (ref "U8") (pin "4") (pinfunction "TCT2_4") (pintype "unspecified"))
    )
    (net (code "67") (name "Net-(U7-CLS)") (class "Default")
      (node (ref "U7") (pin "3") (pinfunction "CLS_3") (pintype "input"))
      (node (ref "U9") (pin "2") (pinfunction "2_2") (pintype "unspecified"))
    )
    (net (code "68") (name "Net-(U7-DET)") (class "Default")
      (node (ref "R7") (pin "2") (pinfunction "2_2") (pintype "unspecified"))
      (node (ref "U7") (pin "2") (pinfunction "DET_2") (pintype "input"))
    )
    (net (code "69") (name "Net-(U7-PG)") (class "Default")
      (node (ref "R9") (pin "1") (pinfunction "1_1") (pintype "input"))
      (node (ref "U7") (pin "6") (pinfunction "PG_6") (pintype "input"))
    )
    (net (code "70") (name "Net-(U7-T2P)") (class "Default")
      (node (ref "R8") (pin "1") (pinfunction "1_1") (pintype "input"))
      (node (ref "U7") (pin "7") (pinfunction "T2P_7") (pintype "input"))
    )
    (net (code "71") (name "Net-(U8-MX1+)") (class "Default")
      (node (ref "RJ2") (pin "1") (pinfunction "1_1") (pintype "unspecified"))
      (node (ref "U8") (pin "23") (pinfunction "MX1+_23") (pintype "unspecified"))
    )
    (net (code "72") (name "Net-(U8-MX1-)") (class "Default")
      (node (ref "RJ2") (pin "2") (pinfunction "2_2") (pintype "unspecified"))
      (node (ref "U8") (pin "22") (pinfunction "MX1-_22") (pintype "unspecified"))
    )
    (net (code "73") (name "Net-(U8-MX2+)") (class "Default")
      (node (ref "RJ2") (pin "3") (pinfunction "3_3") (pintype "unspecified"))
      (node (ref "U8") (pin "20") (pinfunction "MX2+_20") (pintype "unspecified"))
    )
    (net (code "74") (name "Net-(U8-MX2-)") (class "Default")
      (node (ref "RJ2") (pin "6") (pinfunction "6_6") (pintype "unspecified"))
      (node (ref "U8") (pin "19") (pinfunction "MX2-_19") (pintype "unspecified"))
    )
    (net (code "75") (name "Net-(U8-MX4+)") (class "Default")
      (node (ref "RJ2") (pin "7") (pinfunction "7_7") (pintype "unspecified"))
      (node (ref "U8") (pin "14") (pinfunction "MX4+_14") (pintype "unspecified"))
    )
    (net (code "76") (name "Net-(U8-MX4-)") (class "Default")
      (node (ref "RJ2") (pin "8") (pinfunction "8_8") (pintype "unspecified"))
      (node (ref "U8") (pin "13") (pinfunction "MX4-_13") (pintype "unspecified"))
    )
    (net (code "77") (name "Net-(U8-MXT3+)") (class "Default")
      (node (ref "RJ2") (pin "4") (pinfunction "4_4") (pintype "unspecified"))
      (node (ref "U8") (pin "17") (pinfunction "MXT3+_17") (pintype "unspecified"))
    )
    (net (code "78") (name "Net-(U8-MXT3-)") (class "Default")
      (node (ref "RJ2") (pin "5") (pinfunction "5_5") (pintype "unspecified"))
      (node (ref "U8") (pin "16") (pinfunction "MXT3-_16") (pintype "unspecified"))
    )
    (net (code "79") (name "Net-(USB1-CC1)") (class "Default")
      (node (ref "R2") (pin "1") (pinfunction "1_1") (pintype "input"))
      (node (ref "USB1") (pin "4") (pinfunction "CC1_4") (pintype "unspecified"))
    )
    (net (code "80") (name "Net-(USB1-CC2)") (class "Default")
      (node (ref "R1") (pin "1") (pinfunction "1_1") (pintype "input"))
      (node (ref "USB1") (pin "10") (pinfunction "CC2_10") (pintype "unspecified"))
    )
    (net (code "81") (name "PHY0_LED") (class "Default")
      (node (ref "R21") (pin "1") (pinfunction "1_1") (pintype "input"))
      (node (ref "RJ1") (pin "10") (pinfunction "L-_10") (pintype "unspecified"))
      (node (ref "RJ1") (pin "12") (pinfunction "R-_12") (pintype "unspecified"))
    )
    (net (code "82") (name "PHY0_MDI0") (class "Default")
      (node (ref "D2") (pin "3") (pinfunction "C2_3") (pintype "unspecified"))
      (node (ref "U6") (pin "24") (pinfunction "MCT1_24") (pintype "unspecified"))
    )
    (net (code "83") (name "PHY0_MDI1") (class "Default")
      (node (ref "D2") (pin "4") (pinfunction "C1_4") (pintype "unspecified"))
      (node (ref "U6") (pin "21") (pinfunction "MCT2_21") (pintype "unspecified"))
    )
    (net (code "84") (name "PHY0_MDI2") (class "Default")
      (node (ref "D3") (pin "3") (pinfunction "C2_3") (pintype "unspecified"))
      (node (ref "U6") (pin "18") (pinfunction "MCT3_18") (pintype "unspecified"))
    )
    (net (code "85") (name "PHY0_MDI3") (class "Default")
      (node (ref "D3") (pin "4") (pinfunction "C1_4") (pintype "unspecified"))
      (node (ref "U6") (pin "15") (pinfunction "MCT4_15") (pintype "unspecified"))
    )
    (net (code "86") (name "PHY1_LED") (class "Default")
      (node (ref "R22") (pin "1") (pinfunction "1_1") (pintype "input"))
      (node (ref "RJ2") (pin "10") (pinfunction "L-_10") (pintype "unspecified"))
      (node (ref "RJ2") (pin "12") (pinfunction "R-_12") (pintype "unspecified"))
    )
    (net (code "87") (name "PHY1_MDI0") (class "Default")
      (node (ref "D4") (pin "3") (pinfunction "C2_3") (pintype "unspecified"))
      (node (ref "U8") (pin "24") (pinfunction "MCT1_24") (pintype "unspecified"))
    )
    (net (code "88") (name "PHY1_MDI1") (class "Default")
      (node (ref "D4") (pin "4") (pinfunction "C1_4") (pintype "unspecified"))
      (node (ref "U8") (pin "21") (pinfunction "MCT2_21") (pintype "unspecified"))
    )
    (net (code "89") (name "PHY1_MDI2") (class "Default")
      (node (ref "D5") (pin "3") (pinfunction "C2_3") (pintype "unspecified"))
      (node (ref "U8") (pin "18") (pinfunction "MCT3_18") (pintype "unspecified"))
    )
    (net (code "90") (name "PHY1_MDI3") (class "Default")
      (node (ref "D5") (pin "4") (pinfunction "C1_4") (pintype "unspecified"))
      (node (ref "U8") (pin "15") (pinfunction "MCT4_15") (pintype "unspecified"))
    )
    (net (code "91") (name "REFCLK") (class "Default")
      (node (ref "CN3") (pin "2") (pinfunction "2_2") (pintype "unspecified"))
      (node (ref "U1") (pin "6") (pinfunction "REF_CLK0_6") (pintype "unspecified"))
    )
    (net (code "92") (name "SPI-CLK") (class "Default")
      (node (ref "CN2") (pin "10") (pinfunction "10_10") (pintype "unspecified"))
      (node (ref "U1") (pin "27") (pinfunction "SPI_CLK_27") (pintype "unspecified"))
    )
    (net (code "93") (name "SPI-CS1") (class "Default")
      (node (ref "CN2") (pin "11") (pinfunction "11_11") (pintype "unspecified"))
      (node (ref "U1") (pin "26") (pinfunction "SPI_CS1_26") (pintype "unspecified"))
    )
    (net (code "94") (name "SPI-MISO") (class "Default")
      (node (ref "CN2") (pin "9") (pinfunction "9_9") (pintype "unspecified"))
      (node (ref "U1") (pin "28") (pinfunction "SPI_MISO_28") (pintype "unspecified"))
    )
    (net (code "95") (name "SPI-MOSI") (class "Default")
      (node (ref "CN2") (pin "8") (pinfunction "8_8") (pintype "unspecified"))
      (node (ref "U1") (pin "29") (pinfunction "SPI_MOSI_29") (pintype "unspecified"))
    )
    (net (code "96") (name "SYS-LED") (class "Default")
      (node (ref "LED1") (pin "1") (pinfunction "K_1") (pintype "input"))
      (node (ref "U1") (pin "33") (pinfunction "WLED_N_33") (pintype "unspecified"))
    )
    (net (code "97") (name "UART1-RX") (class "Default")
      (node (ref "CN2") (pin "6") (pinfunction "6_6") (pintype "unspecified"))
      (node (ref "R23") (pin "2") (pinfunction "2_2") (pintype "input"))
      (node (ref "U1") (pin "16") (pinfunction "UART_RXD1_16") (pintype "unspecified"))
    )
    (net (code "98") (name "UART1-TX") (class "Default")
      (node (ref "CN2") (pin "5") (pinfunction "5_5") (pintype "unspecified"))
      (node (ref "U1") (pin "15") (pinfunction "UART_TXD1_15") (pintype "unspecified"))
    )
    (net (code "99") (name "USB_DM") (class "Default")
      (node (ref "U1") (pin "55") (pinfunction "USB_DM_55") (pintype "unspecified"))
      (node (ref "USB2") (pin "2") (pinfunction "D-_2") (pintype "unspecified"))
    )
    (net (code "100") (name "USB_DP") (class "Default")
      (node (ref "U1") (pin "54") (pinfunction "USB_DP_54") (pintype "unspecified"))
      (node (ref "USB2") (pin "3") (pinfunction "D+_3") (pintype "unspecified"))
    )
    (net (code "101") (name "VIN") (class "Default")
      (node (ref "C18") (pin "1") (pinfunction "1_1") (pintype "unspecified"))
      (node (ref "C19") (pin "2") (pinfunction "2_2") (pintype "input"))
      (node (ref "D1") (pin "1") (pinfunction "+_1") (pintype "unspecified"))
      (node (ref "D2") (pin "1") (pinfunction "+_1") (pintype "unspecified"))
      (node (ref "D3") (pin "1") (pinfunction "+_1") (pintype "unspecified"))
      (node (ref "D4") (pin "1") (pinfunction "+_1") (pintype "unspecified"))
      (node (ref "D5") (pin "1") (pinfunction "+_1") (pintype "unspecified"))
      (node (ref "R18") (pin "2") (pinfunction "2_2") (pintype "input"))
      (node (ref "R7") (pin "1") (pinfunction "1_1") (pintype "unspecified"))
      (node (ref "R8") (pin "2") (pinfunction "2_2") (pintype "input"))
      (node (ref "R9") (pin "2") (pinfunction "2_2") (pintype "input"))
      (node (ref "U5") (pin "5") (pinfunction "VIN_5") (pintype "input"))
      (node (ref "U7") (pin "1") (pinfunction "VDD_1") (pintype "input"))
    )
    (net (code "102") (name "unconnected-(U1-ANT-Pad22)") (class "Default")
      (node (ref "U1") (pin "22") (pinfunction "ANT_22") (pintype "unspecified+no_connect"))
    )
    (net (code "103") (name "unconnected-(U1-PERST_N-Pad7)") (class "Default")
      (node (ref "U1") (pin "7") (pinfunction "PERST_N_7") (pintype "unspecified+no_connect"))
    )
    (net (code "104") (name "unconnected-(U1-PORST_N-Pad14)") (class "Default")
      (node (ref "U1") (pin "14") (pinfunction "PORST_N_14") (pintype "unspecified+no_connect"))
    )
    (net (code "105") (name "unconnected-(U1-SPI_CS0-Pad5)") (class "Default")
      (node (ref "U1") (pin "5") (pinfunction "SPI_CS0_5") (pintype "unspecified+no_connect"))
    )
    (net (code "106") (name "unconnected-(U2-SQW{slash}OUT-Pad7)") (class "Default")
      (node (ref "U2") (pin "7") (pinfunction "SQW/OUT_7") (pintype "unspecified+no_connect"))
    )
    (net (code "107") (name "unconnected-(U4-RTS#-Pad4)") (class "Default")
      (node (ref "U4") (pin "4") (pinfunction "RTS#_4") (pintype "unspecified+no_connect"))
    )
    (net (code "108") (name "unconnected-(U6-TCT3-Pad7)") (class "Default")
      (node (ref "U6") (pin "7") (pinfunction "TCT3_7") (pintype "unspecified+no_connect"))
    )
    (net (code "109") (name "unconnected-(U6-TCT4-Pad10)") (class "Default")
      (node (ref "U6") (pin "10") (pinfunction "TCT4_10") (pintype "unspecified+no_connect"))
    )
    (net (code "110") (name "unconnected-(U6-TD2+-Pad8)") (class "Default")
      (node (ref "U6") (pin "8") (pinfunction "TD2+_8") (pintype "unspecified+no_connect"))
    )
    (net (code "111") (name "unconnected-(U6-TD3--Pad9)") (class "Default")
      (node (ref "U6") (pin "9") (pinfunction "TD3-_9") (pintype "unspecified+no_connect"))
    )
    (net (code "112") (name "unconnected-(U6-TD4+-Pad11)") (class "Default")
      (node (ref "U6") (pin "11") (pinfunction "TD4+_11") (pintype "unspecified+no_connect"))
    )
    (net (code "113") (name "unconnected-(U6-TD4--Pad12)") (class "Default")
      (node (ref "U6") (pin "12") (pinfunction "TD4-_12") (pintype "unspecified+no_connect"))
    )
    (net (code "114") (name "unconnected-(U8-TCT3-Pad7)") (class "Default")
      (node (ref "U8") (pin "7") (pinfunction "TCT3_7") (pintype "unspecified+no_connect"))
    )
    (net (code "115") (name "unconnected-(U8-TCT4-Pad10)") (class "Default")
      (node (ref "U8") (pin "10") (pinfunction "TCT4_10") (pintype "unspecified+no_connect"))
    )
    (net (code "116") (name "unconnected-(U8-TD2+-Pad8)") (class "Default")
      (node (ref "U8") (pin "8") (pinfunction "TD2+_8") (pintype "unspecified+no_connect"))
    )
    (net (code "117") (name "unconnected-(U8-TD3--Pad9)") (class "Default")
      (node (ref "U8") (pin "9") (pinfunction "TD3-_9") (pintype "unspecified+no_connect"))
    )
    (net (code "118") (name "unconnected-(U8-TD4+-Pad11)") (class "Default")
      (node (ref "U8") (pin "11") (pinfunction "TD4+_11") (pintype "unspecified+no_connect"))
    )
    (net (code "119") (name "unconnected-(U8-TD4--Pad12)") (class "Default")
      (node (ref "U8") (pin "12") (pinfunction "TD4-_12") (pintype "unspecified+no_connect"))
    )
    (net (code "120") (name "unconnected-(USB1-SBU1-Pad9)") (class "Default")
      (node (ref "USB1") (pin "9") (pinfunction "SBU1_9") (pintype "unspecified+no_connect"))
    )
    (net (code "121") (name "unconnected-(USB1-SBU2-Pad3)") (class "Default")
      (node (ref "USB1") (pin "3") (pinfunction "SBU2_3") (pintype "unspecified+no_connect"))
    )
  )
)
